# homeboard6.net
KiCad netlist of a schematic drawn in EAGLE
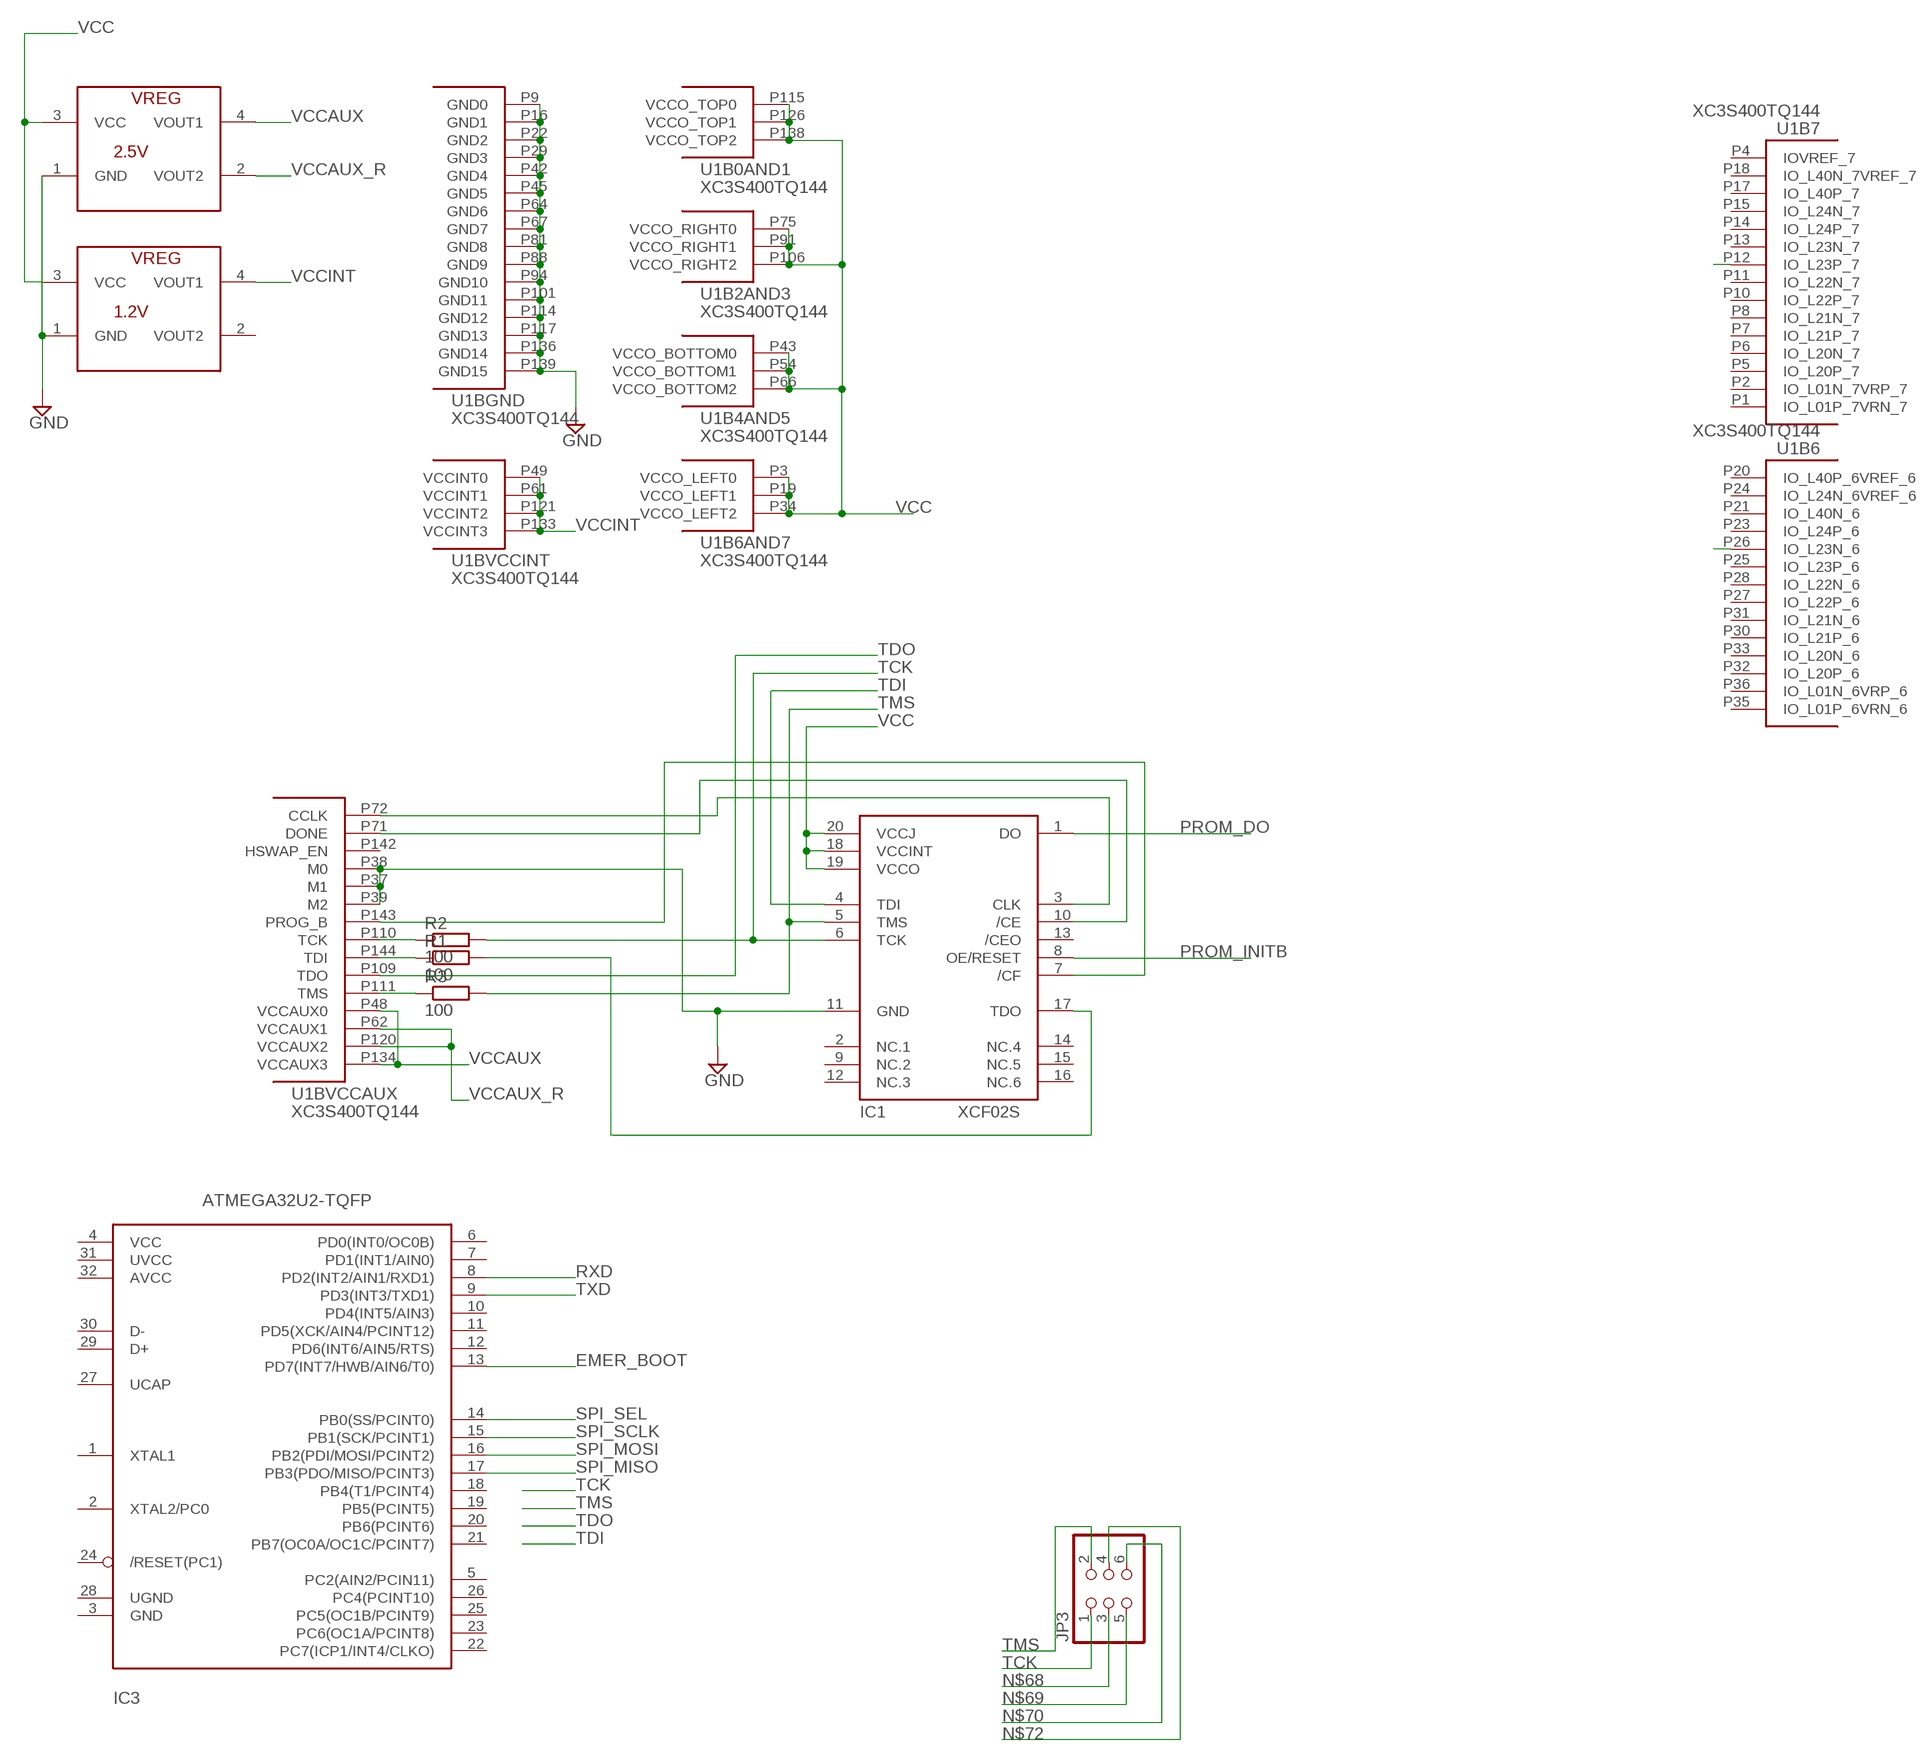
[diagram p0: schematic, sheet 1, part 1 of 3]
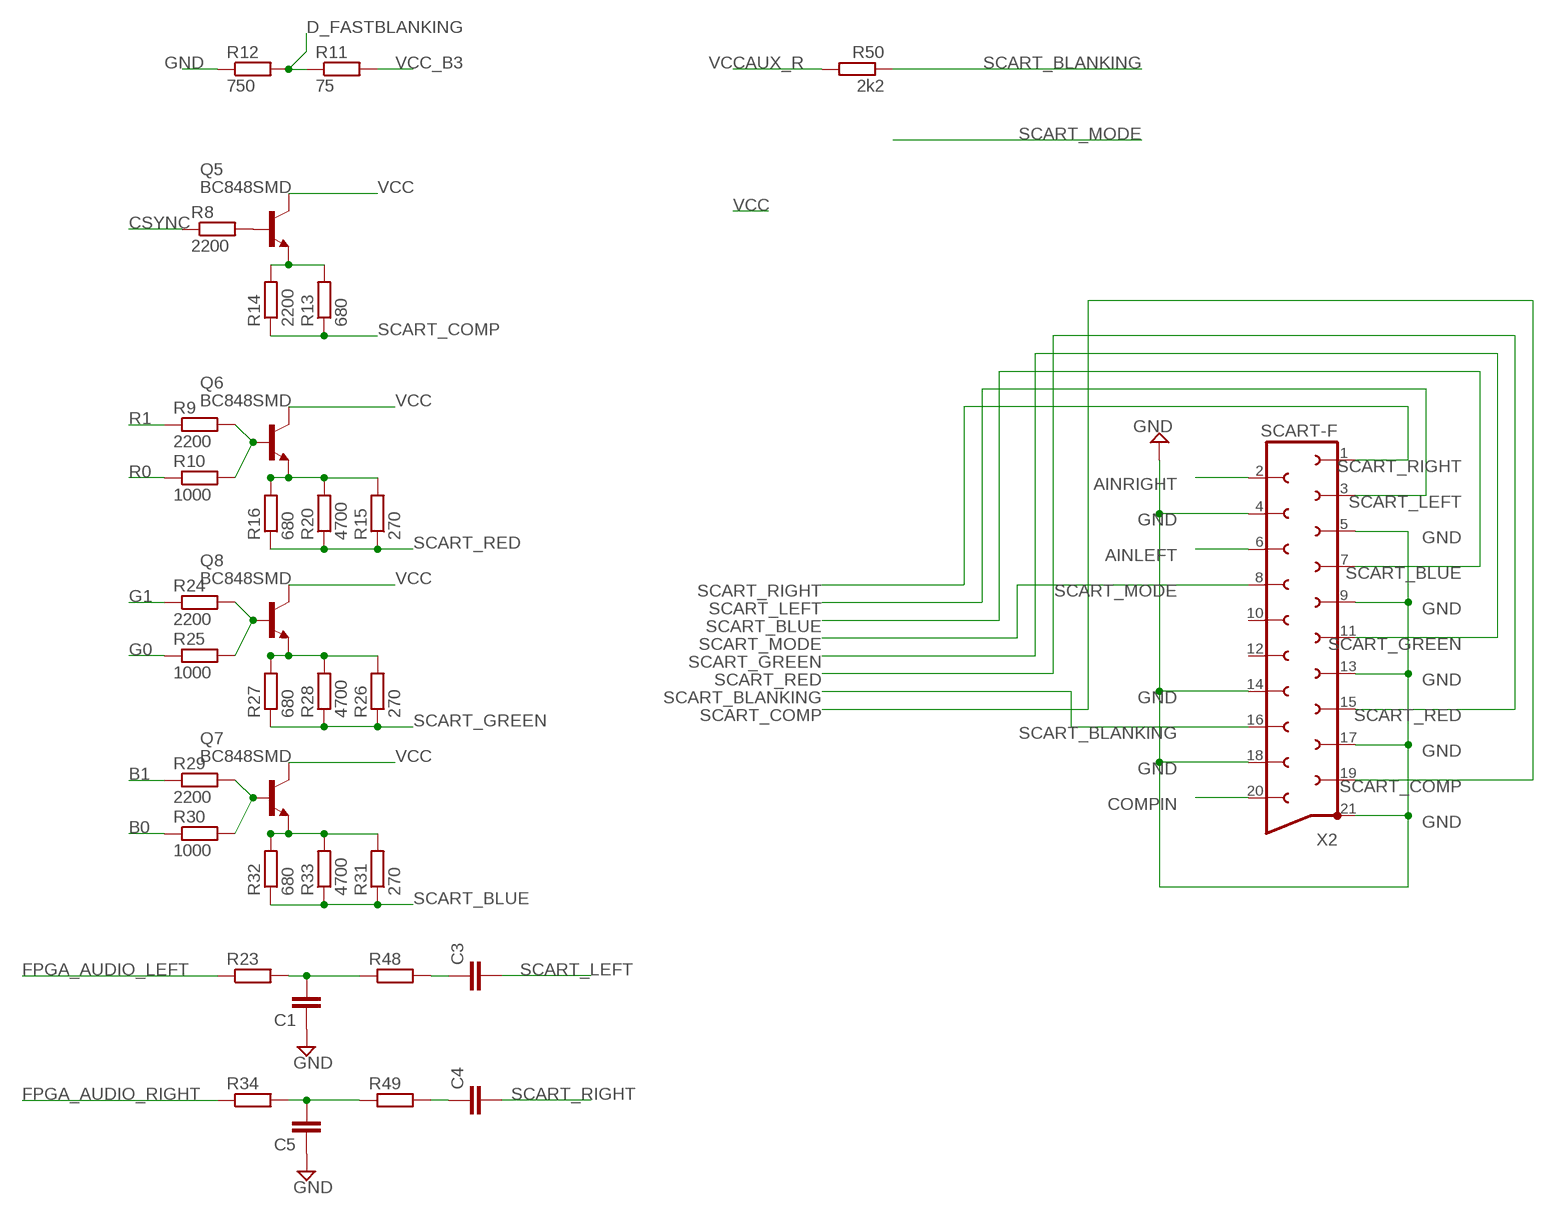
[diagram p1: schematic, sheet 1, part 2 of 3]
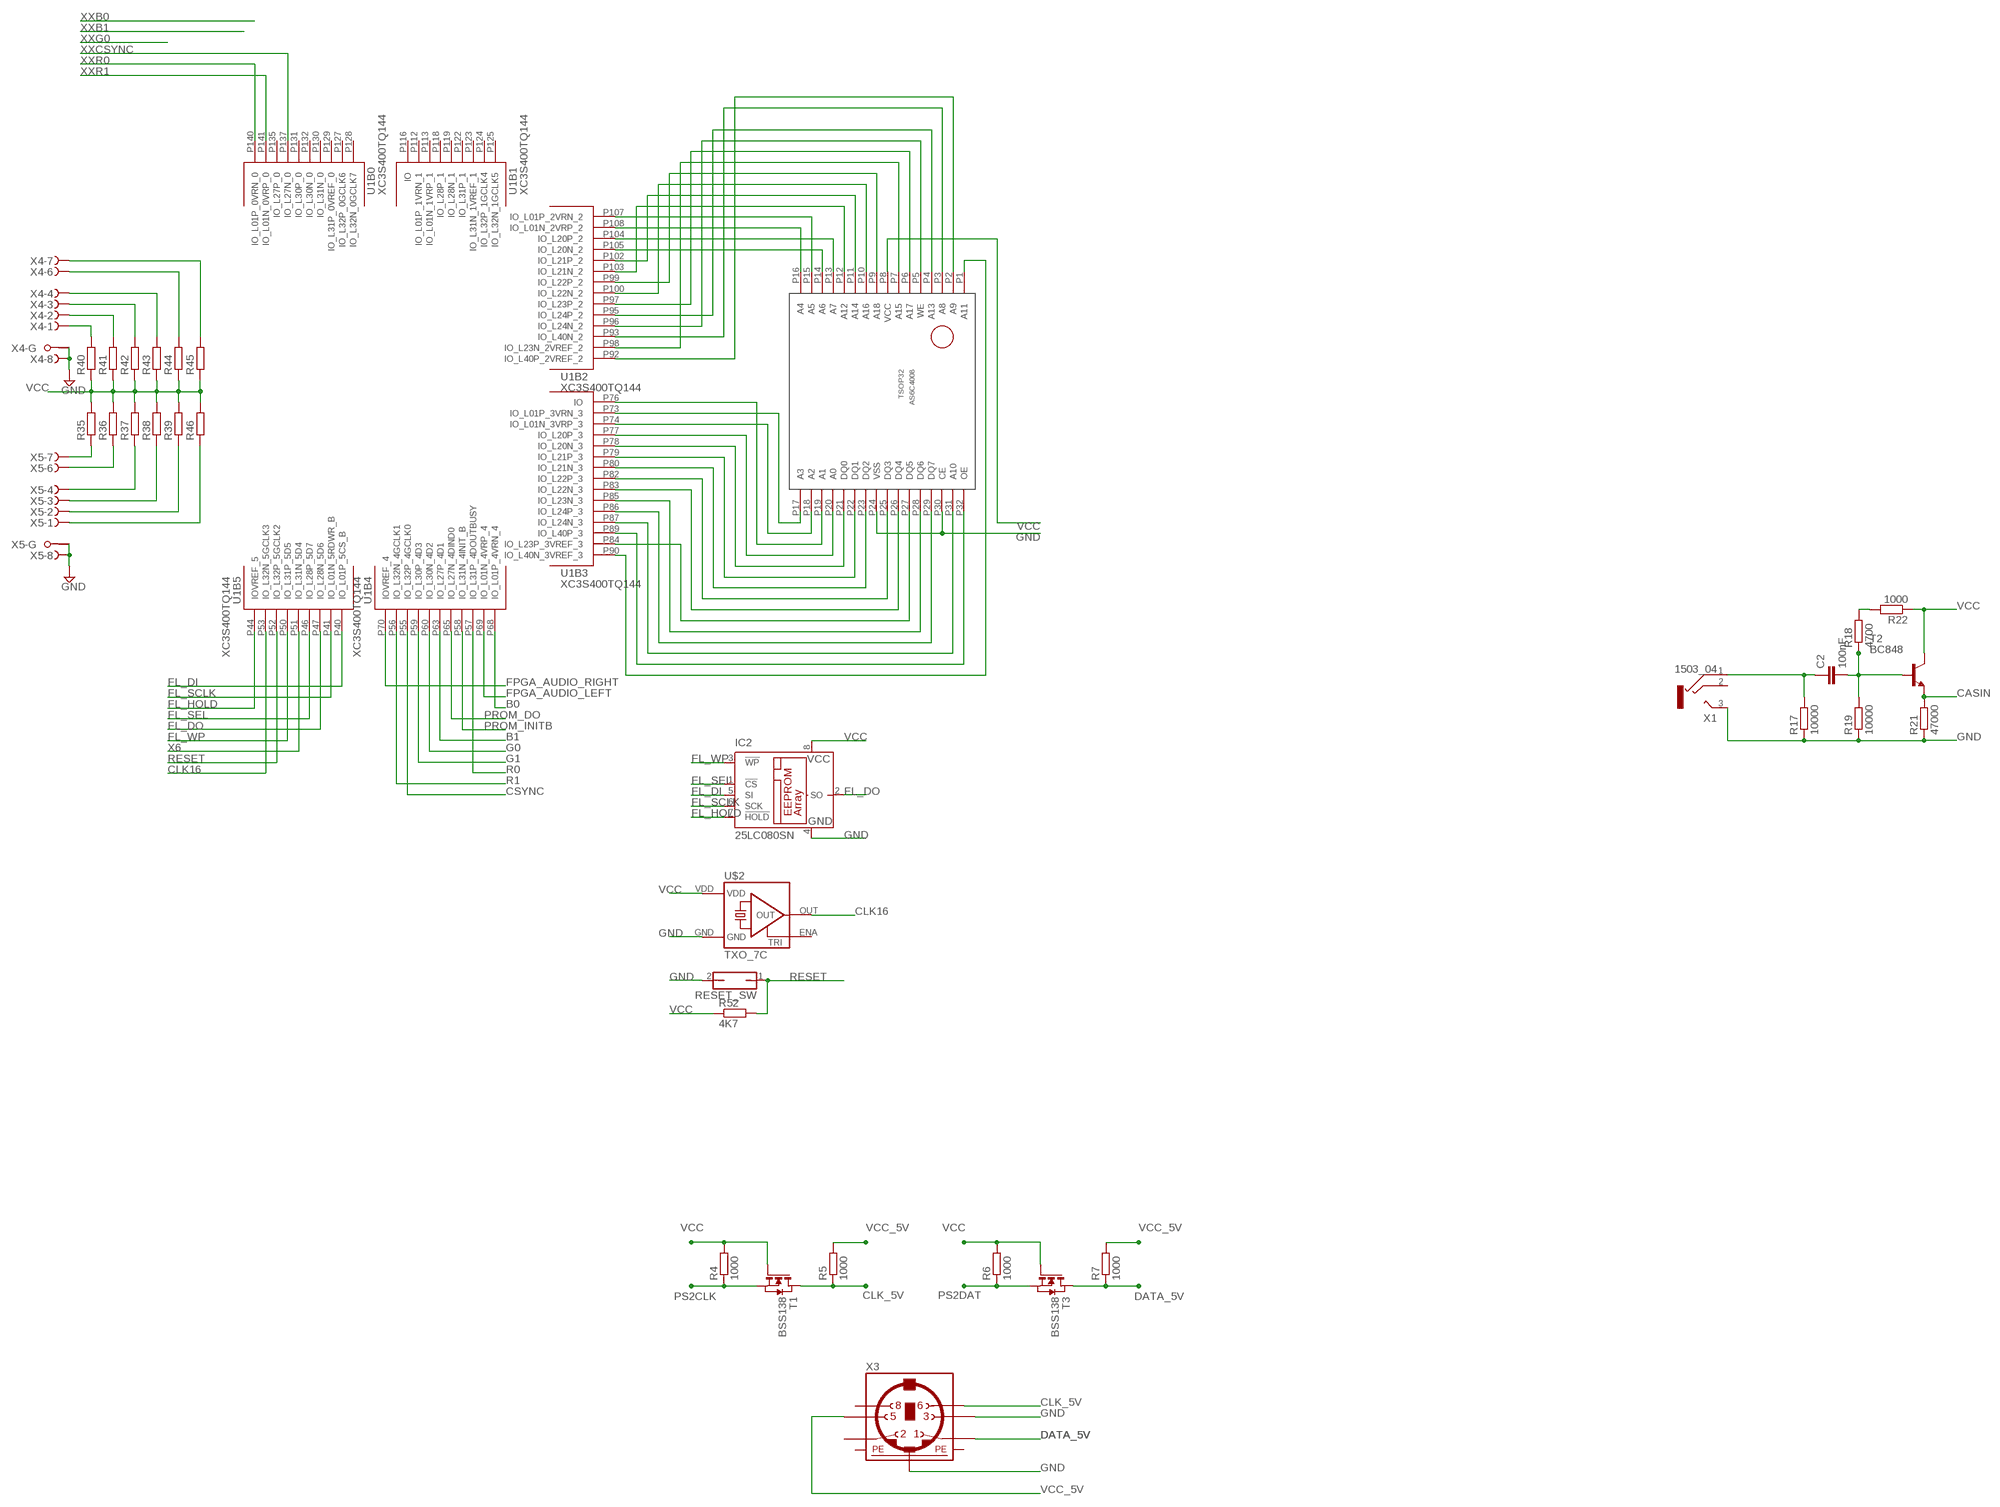
[diagram p2: schematic, sheet 1, part 3 of 3]

(export (version "E")
  (design (tool "Eeschema 10.0.6"))
  (components
    (comp (ref "C1")
      (value "C-EUC0603")
      (footprint "eagle-import:C0603")
      (libsource (lib "eagle-import") (part "C-EUC0603"))
    )
    (comp (ref "C2")
      (value "100nF")
      (footprint "eagle-import:C0603")
      (libsource (lib "eagle-import") (part "C-EUC0603"))
    )
    (comp (ref "C3")
      (value "C-EUC0603")
      (footprint "eagle-import:C0603")
      (libsource (lib "eagle-import") (part "C-EUC0603"))
    )
    (comp (ref "C4")
      (value "C-EUC0603")
      (footprint "eagle-import:C0603")
      (libsource (lib "eagle-import") (part "C-EUC0603"))
    )
    (comp (ref "C5")
      (value "C-EUC0603")
      (footprint "eagle-import:C0603")
      (libsource (lib "eagle-import") (part "C-EUC0603"))
    )
    (comp (ref "IC1")
      (value "XCF02S")
      (footprint "eagle-import:VO20")
      (libsource (lib "eagle-import") (part "XCF02S"))
    )
    (comp (ref "IC2")
      (value "25LC080SN")
      (footprint "eagle-import:SO-08")
      (fields (field (name "MF") "MICROCHIP") (field (name "MPN") "25LC080/SN"))
      (libsource (lib "eagle-import") (part "25SNLC080"))
    )
    (comp (ref "IC3")
      (value "ATMEGA32U2-TQFP")
      (footprint "eagle-import:TQFP32-08")
      (libsource (lib "eagle-import") (part "ATMEGA32U2-TQFP"))
    )
    (comp (ref "JP3")
      (value "PINHD-2X3")
      (footprint "eagle-import:2X03")
      (libsource (lib "eagle-import") (part "PINHD-2X3"))
    )
    (comp (ref "Q5")
      (value "BC848SMD")
      (footprint "eagle-import:SOT23")
      (libsource (lib "eagle-import") (part "BC848SMD"))
    )
    (comp (ref "Q6")
      (value "BC848SMD")
      (footprint "eagle-import:SOT23")
      (libsource (lib "eagle-import") (part "BC848SMD"))
    )
    (comp (ref "Q7")
      (value "BC848SMD")
      (footprint "eagle-import:SOT23")
      (libsource (lib "eagle-import") (part "BC848SMD"))
    )
    (comp (ref "Q8")
      (value "BC848SMD")
      (footprint "eagle-import:SOT23")
      (libsource (lib "eagle-import") (part "BC848SMD"))
    )
    (comp (ref "R1")
      (value "100")
      (footprint "eagle-import:R0805")
      (libsource (lib "eagle-import") (part "R-EU_R0805"))
    )
    (comp (ref "R2")
      (value "100")
      (footprint "eagle-import:R0805")
      (libsource (lib "eagle-import") (part "R-EU_R0805"))
    )
    (comp (ref "R3")
      (value "100")
      (footprint "eagle-import:R0805")
      (libsource (lib "eagle-import") (part "R-EU_R0805"))
    )
    (comp (ref "R4")
      (value "1000")
      (footprint "eagle-import:R0805")
      (libsource (lib "eagle-import") (part "R-EU_R0805"))
    )
    (comp (ref "R5")
      (value "1000")
      (footprint "eagle-import:R0805")
      (libsource (lib "eagle-import") (part "R-EU_R0805"))
    )
    (comp (ref "R6")
      (value "1000")
      (footprint "eagle-import:R0805")
      (libsource (lib "eagle-import") (part "R-EU_R0805"))
    )
    (comp (ref "R7")
      (value "1000")
      (footprint "eagle-import:R0805")
      (libsource (lib "eagle-import") (part "R-EU_R0805"))
    )
    (comp (ref "R8")
      (value "2200")
      (footprint "eagle-import:R0805")
      (libsource (lib "eagle-import") (part "R-EU_R0805"))
    )
    (comp (ref "R9")
      (value "2200")
      (footprint "eagle-import:R0805")
      (libsource (lib "eagle-import") (part "R-EU_R0805"))
    )
    (comp (ref "R10")
      (value "1000")
      (footprint "eagle-import:R0805")
      (libsource (lib "eagle-import") (part "R-EU_R0805"))
    )
    (comp (ref "R11")
      (value "75")
      (footprint "eagle-import:R0805")
      (libsource (lib "eagle-import") (part "R-EU_R0805"))
    )
    (comp (ref "R12")
      (value "750")
      (footprint "eagle-import:R0805")
      (libsource (lib "eagle-import") (part "R-EU_R0805"))
    )
    (comp (ref "R13")
      (value "680")
      (footprint "eagle-import:R0805")
      (libsource (lib "eagle-import") (part "R-EU_R0805"))
    )
    (comp (ref "R14")
      (value "2200")
      (footprint "eagle-import:R0805")
      (libsource (lib "eagle-import") (part "R-EU_R0805"))
    )
    (comp (ref "R15")
      (value "270")
      (footprint "eagle-import:R0805")
      (libsource (lib "eagle-import") (part "R-EU_R0805"))
    )
    (comp (ref "R16")
      (value "680")
      (footprint "eagle-import:R0805")
      (libsource (lib "eagle-import") (part "R-EU_R0805"))
    )
    (comp (ref "R17")
      (value "10000")
      (footprint "eagle-import:R0805")
      (libsource (lib "eagle-import") (part "R-EU_R0805"))
    )
    (comp (ref "R18")
      (value "4700")
      (footprint "eagle-import:R0805")
      (libsource (lib "eagle-import") (part "R-EU_R0805"))
    )
    (comp (ref "R19")
      (value "10000")
      (footprint "eagle-import:R0805")
      (libsource (lib "eagle-import") (part "R-EU_R0805"))
    )
    (comp (ref "R20")
      (value "4700")
      (footprint "eagle-import:R0805")
      (libsource (lib "eagle-import") (part "R-EU_R0805"))
    )
    (comp (ref "R21")
      (value "47000")
      (footprint "eagle-import:R0805")
      (libsource (lib "eagle-import") (part "R-EU_R0805"))
    )
    (comp (ref "R22")
      (value "1000")
      (footprint "eagle-import:R0805")
      (libsource (lib "eagle-import") (part "R-EU_R0805"))
    )
    (comp (ref "R23")
      (value "R-EU_M0805")
      (footprint "eagle-import:M0805")
      (libsource (lib "eagle-import") (part "resistor_R-EU_M0805"))
    )
    (comp (ref "R24")
      (value "2200")
      (footprint "eagle-import:R0805")
      (libsource (lib "eagle-import") (part "R-EU_R0805"))
    )
    (comp (ref "R25")
      (value "1000")
      (footprint "eagle-import:R0805")
      (libsource (lib "eagle-import") (part "R-EU_R0805"))
    )
    (comp (ref "R26")
      (value "270")
      (footprint "eagle-import:R0805")
      (libsource (lib "eagle-import") (part "R-EU_R0805"))
    )
    (comp (ref "R27")
      (value "680")
      (footprint "eagle-import:R0805")
      (libsource (lib "eagle-import") (part "R-EU_R0805"))
    )
    (comp (ref "R28")
      (value "4700")
      (footprint "eagle-import:R0805")
      (libsource (lib "eagle-import") (part "R-EU_R0805"))
    )
    (comp (ref "R29")
      (value "2200")
      (footprint "eagle-import:R0805")
      (libsource (lib "eagle-import") (part "R-EU_R0805"))
    )
    (comp (ref "R30")
      (value "1000")
      (footprint "eagle-import:R0805")
      (libsource (lib "eagle-import") (part "R-EU_R0805"))
    )
    (comp (ref "R31")
      (value "270")
      (footprint "eagle-import:R0805")
      (libsource (lib "eagle-import") (part "R-EU_R0805"))
    )
    (comp (ref "R32")
      (value "680")
      (footprint "eagle-import:R0805")
      (libsource (lib "eagle-import") (part "R-EU_R0805"))
    )
    (comp (ref "R33")
      (value "4700")
      (footprint "eagle-import:R0805")
      (libsource (lib "eagle-import") (part "R-EU_R0805"))
    )
    (comp (ref "R34")
      (value "R-EU_M0805")
      (footprint "eagle-import:M0805")
      (libsource (lib "eagle-import") (part "resistor_R-EU_M0805"))
    )
    (comp (ref "R35")
      (value "R-EU_M0805")
      (footprint "eagle-import:M0805")
      (libsource (lib "eagle-import") (part "resistor_R-EU_M0805"))
    )
    (comp (ref "R36")
      (value "R-EU_M0805")
      (footprint "eagle-import:M0805")
      (libsource (lib "eagle-import") (part "resistor_R-EU_M0805"))
    )
    (comp (ref "R37")
      (value "R-EU_M0805")
      (footprint "eagle-import:M0805")
      (libsource (lib "eagle-import") (part "resistor_R-EU_M0805"))
    )
    (comp (ref "R38")
      (value "R-EU_M0805")
      (footprint "eagle-import:M0805")
      (libsource (lib "eagle-import") (part "resistor_R-EU_M0805"))
    )
    (comp (ref "R39")
      (value "R-EU_M0805")
      (footprint "eagle-import:M0805")
      (libsource (lib "eagle-import") (part "resistor_R-EU_M0805"))
    )
    (comp (ref "R40")
      (value "R-EU_M0805")
      (footprint "eagle-import:M0805")
      (libsource (lib "eagle-import") (part "resistor_R-EU_M0805"))
    )
    (comp (ref "R41")
      (value "R-EU_M0805")
      (footprint "eagle-import:M0805")
      (libsource (lib "eagle-import") (part "resistor_R-EU_M0805"))
    )
    (comp (ref "R42")
      (value "R-EU_M0805")
      (footprint "eagle-import:M0805")
      (libsource (lib "eagle-import") (part "resistor_R-EU_M0805"))
    )
    (comp (ref "R43")
      (value "R-EU_M0805")
      (footprint "eagle-import:M0805")
      (libsource (lib "eagle-import") (part "resistor_R-EU_M0805"))
    )
    (comp (ref "R44")
      (value "R-EU_M0805")
      (footprint "eagle-import:M0805")
      (libsource (lib "eagle-import") (part "resistor_R-EU_M0805"))
    )
    (comp (ref "R45")
      (value "R-EU_M0805")
      (footprint "eagle-import:M0805")
      (libsource (lib "eagle-import") (part "resistor_R-EU_M0805"))
    )
    (comp (ref "R46")
      (value "R-EU_M0805")
      (footprint "eagle-import:M0805")
      (libsource (lib "eagle-import") (part "resistor_R-EU_M0805"))
    )
    (comp (ref "R48")
      (value "R-EU_M0805")
      (footprint "eagle-import:M0805")
      (libsource (lib "eagle-import") (part "resistor_R-EU_M0805"))
    )
    (comp (ref "R49")
      (value "R-EU_M0805")
      (footprint "eagle-import:M0805")
      (libsource (lib "eagle-import") (part "resistor_R-EU_M0805"))
    )
    (comp (ref "R50")
      (value "2k2")
      (footprint "eagle-import:M0805")
      (libsource (lib "eagle-import") (part "resistor_R-EU_M0805"))
    )
    (comp (ref "R52")
      (value "4K7")
      (footprint "eagle-import:M0805")
      (libsource (lib "eagle-import") (part "resistor_R-EU_M0805"))
    )
    (comp (ref "REG1.2")
      (value "1.2V")
      (footprint "eagle-import:SOT223")
      (libsource (lib "eagle-import") (part "NX1117"))
    )
    (comp (ref "REG2.5")
      (value "2.5V")
      (footprint "eagle-import:SOT223")
      (libsource (lib "eagle-import") (part "NX1117"))
    )
    (comp (ref "RESET_SW")
      (value "JP1Q")
      (footprint "eagle-import:JP1")
      (libsource (lib "eagle-import") (part "JP1Q"))
    )
    (comp (ref "T1")
      (value "BSS138")
      (footprint "eagle-import:SOT-23")
      (libsource (lib "eagle-import") (part "NMOSSOT23"))
    )
    (comp (ref "T2")
      (value "BC848")
      (footprint "eagle-import:SOT23")
      (libsource (lib "eagle-import") (part "BC848"))
    )
    (comp (ref "T3")
      (value "BSS138")
      (footprint "eagle-import:SOT-23")
      (libsource (lib "eagle-import") (part "NMOSSOT23"))
    )
    (comp (ref "U$1")
      (value "AS6C4008")
      (footprint "eagle-import:TSOP32")
      (libsource (lib "eagle-import") (part "AS6C4008"))
    )
    (comp (ref "U$2")
      (value "TXO_7C")
      (footprint "eagle-import:OSC_7C")
      (libsource (lib "eagle-import") (part "TXO_7C"))
    )
    (comp (ref "U1")
      (value "XC3S400TQ144")
      (footprint "eagle-import:TQ144")
      (libsource (lib "eagle-import") (part "XC3S400TQ144"))
    )
    (comp (ref "X1")
      (value "1503_04")
      (footprint "eagle-import:1503_04")
      (libsource (lib "eagle-import") (part "1503_04"))
    )
    (comp (ref "X2")
      (value "SCART-F")
      (footprint "eagle-import:SCART-F")
      (libsource (lib "eagle-import") (part "SCART-F"))
    )
    (comp (ref "X3")
      (value "MINI_DIN_6")
      (footprint "eagle-import:M_DIN6")
      (libsource (lib "eagle-import") (part "MINI_DIN_6"))
    )
    (comp (ref "X4")
      (value "F09HPS")
      (footprint "eagle-import:F09HP")
      (libsource (lib "eagle-import") (part "F09HPS"))
    )
    (comp (ref "X5")
      (value "F09HPS")
      (footprint "eagle-import:F09HP")
      (libsource (lib "eagle-import") (part "F09HPS"))
    )
  )
  (nets
    (net (code "1") (name "/AINLEFT") (class "Default")
      (node (ref "X2") (pin "6") (pinfunction "6_6") (pintype "passive"))
    )
    (net (code "2") (name "/AINRIGHT") (class "Default")
      (node (ref "X2") (pin "2") (pinfunction "2_2") (pintype "passive"))
    )
    (net (code "3") (name "/B0") (class "Default")
      (node (ref "R30") (pin "1") (pinfunction "1_1") (pintype "passive"))
      (node (ref "U1") (pin "P68") (pinfunction "IO_L01P_4VRN_4_P68") (pintype "bidirectional"))
    )
    (net (code "4") (name "/B1") (class "Default")
      (node (ref "R29") (pin "1") (pinfunction "1_1") (pintype "passive"))
      (node (ref "U1") (pin "P63") (pinfunction "IO_L27P_4D1_P63") (pintype "bidirectional"))
    )
    (net (code "5") (name "/CASIN") (class "Default")
      (node (ref "R21") (pin "2") (pinfunction "2_2") (pintype "passive"))
      (node (ref "T2") (pin "2") (pinfunction "E_2") (pintype "passive"))
    )
    (net (code "6") (name "/CLK16") (class "Default")
      (node (ref "U$2") (pin "OUT") (pinfunction "OUT_OUT") (pintype "output"))
      (node (ref "U1") (pin "P53") (pinfunction "IO_L32N_5GCLK3_P53") (pintype "bidirectional"))
    )
    (net (code "7") (name "/CLK_5V") (class "Default")
      (node (ref "R5") (pin "1") (pinfunction "1_1") (pintype "passive"))
      (node (ref "T1") (pin "1") (pinfunction "D_1") (pintype "passive"))
      (node (ref "X3") (pin "6") (pinfunction "6_6") (pintype "passive"))
    )
    (net (code "8") (name "/COMPIN") (class "Default")
      (node (ref "X2") (pin "20") (pinfunction "20_20") (pintype "passive"))
    )
    (net (code "9") (name "/CSYNC") (class "Default")
      (node (ref "R8") (pin "1") (pinfunction "1_1") (pintype "passive"))
      (node (ref "U1") (pin "P55") (pinfunction "IO_L32P_4GCLK0_P55") (pintype "bidirectional"))
    )
    (net (code "10") (name "/DATA_5V") (class "Default")
      (node (ref "R7") (pin "1") (pinfunction "1_1") (pintype "passive"))
      (node (ref "T3") (pin "1") (pinfunction "D_1") (pintype "passive"))
      (node (ref "X3") (pin "1") (pinfunction "1_1") (pintype "passive"))
    )
    (net (code "11") (name "/D_FASTBLANKING") (class "Default")
      (node (ref "R11") (pin "1") (pinfunction "1_1") (pintype "passive"))
      (node (ref "R12") (pin "2") (pinfunction "2_2") (pintype "passive"))
    )
    (net (code "12") (name "/EMER_BOOT") (class "Default")
      (node (ref "IC3") (pin "13") (pinfunction "PD7(INT7/HWB/AIN6/T0)_13") (pintype "bidirectional"))
    )
    (net (code "13") (name "/FL_DI") (class "Default")
      (node (ref "IC2") (pin "5") (pinfunction "SI_5") (pintype "input"))
      (node (ref "U1") (pin "P40") (pinfunction "IO_L01P_5CS_B_P40") (pintype "bidirectional"))
    )
    (net (code "14") (name "/FL_DO") (class "Default")
      (node (ref "IC2") (pin "2") (pinfunction "SO_2") (pintype "bidirectional"))
      (node (ref "U1") (pin "P47") (pinfunction "IO_L28N_5D6_P47") (pintype "bidirectional"))
    )
    (net (code "15") (name "/FL_HOLD") (class "Default")
      (node (ref "IC2") (pin "7") (pinfunction "~{HOLD}_7") (pintype "input"))
      (node (ref "U1") (pin "P44") (pinfunction "IOVREF_5_P44") (pintype "bidirectional"))
    )
    (net (code "16") (name "/FL_SCLK") (class "Default")
      (node (ref "IC2") (pin "6") (pinfunction "SCK_6") (pintype "input"))
      (node (ref "U1") (pin "P41") (pinfunction "IO_L01N_5RDWR_B_P41") (pintype "bidirectional"))
    )
    (net (code "17") (name "/FL_SEL") (class "Default")
      (node (ref "IC2") (pin "1") (pinfunction "~{CS}_1") (pintype "input"))
      (node (ref "U1") (pin "P46") (pinfunction "IO_L28P_5D7_P46") (pintype "bidirectional"))
    )
    (net (code "18") (name "/FL_WP") (class "Default")
      (node (ref "IC2") (pin "3") (pinfunction "~{WP}_3") (pintype "input"))
      (node (ref "U1") (pin "P50") (pinfunction "IO_L31P_5D5_P50") (pintype "bidirectional"))
    )
    (net (code "19") (name "/FPGA_AUDIO_LEFT") (class "Default")
      (node (ref "R23") (pin "1") (pinfunction "1_1") (pintype "passive"))
      (node (ref "U1") (pin "P69") (pinfunction "IO_L01N_4VRP_4_P69") (pintype "bidirectional"))
    )
    (net (code "20") (name "/FPGA_AUDIO_RIGHT") (class "Default")
      (node (ref "R34") (pin "1") (pinfunction "1_1") (pintype "passive"))
      (node (ref "U1") (pin "P70") (pinfunction "IOVREF_4_P70") (pintype "bidirectional"))
    )
    (net (code "21") (name "/G0") (class "Default")
      (node (ref "R25") (pin "1") (pinfunction "1_1") (pintype "passive"))
      (node (ref "U1") (pin "P60") (pinfunction "IO_L30N_4D2_P60") (pintype "bidirectional"))
    )
    (net (code "22") (name "/G1") (class "Default")
      (node (ref "R24") (pin "1") (pinfunction "1_1") (pintype "passive"))
      (node (ref "U1") (pin "P59") (pinfunction "IO_L30P_4D3_P59") (pintype "bidirectional"))
    )
    (net (code "23") (name "/N$68") (class "Default")
      (node (ref "JP3") (pin "3") (pinfunction "3_3") (pintype "passive"))
    )
    (net (code "24") (name "/N$69") (class "Default")
      (node (ref "JP3") (pin "5") (pinfunction "5_5") (pintype "passive"))
    )
    (net (code "25") (name "/N$70") (class "Default")
      (node (ref "JP3") (pin "6") (pinfunction "6_6") (pintype "passive"))
    )
    (net (code "26") (name "/N$72") (class "Default")
      (node (ref "JP3") (pin "4") (pinfunction "4_4") (pintype "passive"))
    )
    (net (code "27") (name "/PE1") (class "Default")
      (node (ref "X3") (pin "SH1") (pinfunction "PE1_SH1") (pintype "power_in"))
    )
    (net (code "28") (name "/PE3") (class "Default")
      (node (ref "X3") (pin "SH3") (pinfunction "PE3_SH3") (pintype "power_in"))
    )
    (net (code "29") (name "/PROM_DO") (class "Default")
      (node (ref "IC1") (pin "1") (pinfunction "DO_1") (pintype "bidirectional"))
      (node (ref "U1") (pin "P65") (pinfunction "IO_L27N_4DIND0_P65") (pintype "bidirectional"))
    )
    (net (code "30") (name "/PROM_INITB") (class "Default")
      (node (ref "IC1") (pin "8") (pinfunction "OE/RESET_8") (pintype "bidirectional"))
      (node (ref "U1") (pin "P58") (pinfunction "IO_L31N_4INIT_B_P58") (pintype "bidirectional"))
    )
    (net (code "31") (name "/PS2CLK") (class "Default")
      (node (ref "R4") (pin "1") (pinfunction "1_1") (pintype "passive"))
      (node (ref "T1") (pin "2") (pinfunction "S_2") (pintype "passive"))
    )
    (net (code "32") (name "/PS2DAT") (class "Default")
      (node (ref "R6") (pin "1") (pinfunction "1_1") (pintype "passive"))
      (node (ref "T3") (pin "2") (pinfunction "S_2") (pintype "passive"))
    )
    (net (code "33") (name "/R0") (class "Default")
      (node (ref "R10") (pin "1") (pinfunction "1_1") (pintype "passive"))
      (node (ref "U1") (pin "P57") (pinfunction "IO_L31P_4DOUTBUSY_P57") (pintype "bidirectional"))
    )
    (net (code "34") (name "/R1") (class "Default")
      (node (ref "R9") (pin "1") (pinfunction "1_1") (pintype "passive"))
      (node (ref "U1") (pin "P56") (pinfunction "IO_L32N_4GCLK1_P56") (pintype "bidirectional"))
    )
    (net (code "35") (name "/RESET") (class "Default")
      (node (ref "R52") (pin "2") (pinfunction "2_2") (pintype "passive"))
      (node (ref "RESET_SW") (pin "1") (pinfunction "1_1") (pintype "passive"))
      (node (ref "U1") (pin "P52") (pinfunction "IO_L32P_5GCLK2_P52") (pintype "bidirectional"))
    )
    (net (code "36") (name "/RXD") (class "Default")
      (node (ref "IC3") (pin "8") (pinfunction "PD2(INT2/AIN1/RXD1)_8") (pintype "bidirectional"))
    )
    (net (code "37") (name "/SCART_BLANKING") (class "Default")
      (node (ref "R50") (pin "1") (pinfunction "1_1") (pintype "passive"))
      (node (ref "X2") (pin "16") (pinfunction "16_16") (pintype "passive"))
    )
    (net (code "38") (name "/SCART_BLUE") (class "Default")
      (node (ref "R31") (pin "1") (pinfunction "1_1") (pintype "passive"))
      (node (ref "R32") (pin "1") (pinfunction "1_1") (pintype "passive"))
      (node (ref "R33") (pin "1") (pinfunction "1_1") (pintype "passive"))
      (node (ref "X2") (pin "7") (pinfunction "7_7") (pintype "passive"))
    )
    (net (code "39") (name "/SCART_COMP") (class "Default")
      (node (ref "R13") (pin "1") (pinfunction "1_1") (pintype "passive"))
      (node (ref "R14") (pin "1") (pinfunction "1_1") (pintype "passive"))
      (node (ref "X2") (pin "19") (pinfunction "19_19") (pintype "passive"))
    )
    (net (code "40") (name "/SCART_GREEN") (class "Default")
      (node (ref "R26") (pin "1") (pinfunction "1_1") (pintype "passive"))
      (node (ref "R27") (pin "1") (pinfunction "1_1") (pintype "passive"))
      (node (ref "R28") (pin "1") (pinfunction "1_1") (pintype "passive"))
      (node (ref "X2") (pin "11") (pinfunction "11_11") (pintype "passive"))
    )
    (net (code "41") (name "/SCART_LEFT") (class "Default")
      (node (ref "C3") (pin "2") (pinfunction "2_2") (pintype "passive"))
      (node (ref "X2") (pin "3") (pinfunction "3_3") (pintype "passive"))
    )
    (net (code "42") (name "/SCART_MODE") (class "Default")
      (node (ref "X2") (pin "8") (pinfunction "8_8") (pintype "passive"))
    )
    (net (code "43") (name "/SCART_RED") (class "Default")
      (node (ref "R15") (pin "1") (pinfunction "1_1") (pintype "passive"))
      (node (ref "R16") (pin "1") (pinfunction "1_1") (pintype "passive"))
      (node (ref "R20") (pin "1") (pinfunction "1_1") (pintype "passive"))
      (node (ref "X2") (pin "15") (pinfunction "15_15") (pintype "passive"))
    )
    (net (code "44") (name "/SCART_RIGHT") (class "Default")
      (node (ref "C4") (pin "2") (pinfunction "2_2") (pintype "passive"))
      (node (ref "X2") (pin "1") (pinfunction "1_1") (pintype "passive"))
    )
    (net (code "45") (name "/SPI_MISO") (class "Default")
      (node (ref "IC3") (pin "17") (pinfunction "PB3(PDO/MISO/PCINT3)_17") (pintype "bidirectional"))
    )
    (net (code "46") (name "/SPI_MOSI") (class "Default")
      (node (ref "IC3") (pin "16") (pinfunction "PB2(PDI/MOSI/PCINT2)_16") (pintype "bidirectional"))
    )
    (net (code "47") (name "/SPI_SCLK") (class "Default")
      (node (ref "IC3") (pin "15") (pinfunction "PB1(SCK/PCINT1)_15") (pintype "bidirectional"))
    )
    (net (code "48") (name "/SPI_SEL") (class "Default")
      (node (ref "IC3") (pin "14") (pinfunction "PB0(SS/PCINT0)_14") (pintype "bidirectional"))
    )
    (net (code "49") (name "/TCK") (class "Default")
      (node (ref "IC1") (pin "6") (pinfunction "TCK_6") (pintype "bidirectional"))
      (node (ref "JP3") (pin "1") (pinfunction "1_1") (pintype "passive"))
      (node (ref "R2") (pin "2") (pinfunction "2_2") (pintype "passive"))
    )
    (net (code "50") (name "/TDI") (class "Default")
      (node (ref "IC1") (pin "4") (pinfunction "TDI_4") (pintype "bidirectional"))
    )
    (net (code "51") (name "/TDO") (class "Default")
      (node (ref "U1") (pin "P109") (pinfunction "TDO_P109") (pintype "bidirectional"))
    )
    (net (code "52") (name "/TMS") (class "Default")
      (node (ref "IC1") (pin "5") (pinfunction "TMS_5") (pintype "bidirectional"))
      (node (ref "JP3") (pin "2") (pinfunction "2_2") (pintype "passive"))
      (node (ref "R3") (pin "2") (pinfunction "2_2") (pintype "passive"))
    )
    (net (code "53") (name "/TXD") (class "Default")
      (node (ref "IC3") (pin "9") (pinfunction "PD3(INT3/TXD1)_9") (pintype "bidirectional"))
    )
    (net (code "54") (name "/VCC") (class "Default")
      (node (ref "IC1") (pin "18") (pinfunction "VCCINT_18") (pintype "bidirectional"))
      (node (ref "IC1") (pin "19") (pinfunction "VCCO_19") (pintype "bidirectional"))
      (node (ref "IC1") (pin "20") (pinfunction "VCCJ_20") (pintype "bidirectional"))
      (node (ref "IC2") (pin "8") (pinfunction "VCC_8") (pintype "power_in"))
      (node (ref "Q5") (pin "3") (pinfunction "C_3") (pintype "passive"))
      (node (ref "Q6") (pin "3") (pinfunction "C_3") (pintype "passive"))
      (node (ref "Q7") (pin "3") (pinfunction "C_3") (pintype "passive"))
      (node (ref "Q8") (pin "3") (pinfunction "C_3") (pintype "passive"))
      (node (ref "R22") (pin "1") (pinfunction "1_1") (pintype "passive"))
      (node (ref "R35") (pin "2") (pinfunction "2_2") (pintype "passive"))
      (node (ref "R36") (pin "2") (pinfunction "2_2") (pintype "passive"))
      (node (ref "R37") (pin "2") (pinfunction "2_2") (pintype "passive"))
      (node (ref "R38") (pin "2") (pinfunction "2_2") (pintype "passive"))
      (node (ref "R39") (pin "2") (pinfunction "2_2") (pintype "passive"))
      (node (ref "R4") (pin "2") (pinfunction "2_2") (pintype "passive"))
      (node (ref "R40") (pin "1") (pinfunction "1_1") (pintype "passive"))
      (node (ref "R41") (pin "1") (pinfunction "1_1") (pintype "passive"))
      (node (ref "R42") (pin "1") (pinfunction "1_1") (pintype "passive"))
      (node (ref "R43") (pin "1") (pinfunction "1_1") (pintype "passive"))
      (node (ref "R44") (pin "1") (pinfunction "1_1") (pintype "passive"))
      (node (ref "R45") (pin "1") (pinfunction "1_1") (pintype "passive"))
      (node (ref "R46") (pin "2") (pinfunction "2_2") (pintype "passive"))
      (node (ref "R52") (pin "1") (pinfunction "1_1") (pintype "passive"))
      (node (ref "R6") (pin "2") (pinfunction "2_2") (pintype "passive"))
      (node (ref "REG1.2") (pin "3") (pinfunction "VCC_3") (pintype "bidirectional"))
      (node (ref "REG2.5") (pin "3") (pinfunction "VCC_3") (pintype "bidirectional"))
      (node (ref "T1") (pin "3") (pinfunction "G_3") (pintype "passive"))
      (node (ref "T2") (pin "3") (pinfunction "C_3") (pintype "passive"))
      (node (ref "T3") (pin "3") (pinfunction "G_3") (pintype "passive"))
      (node (ref "U$1") (pin "P8") (pinfunction "VCC_P8") (pintype "bidirectional"))
      (node (ref "U$2") (pin "VDD") (pinfunction "VDD_VDD") (pintype "power_in"))
      (node (ref "U1") (pin "P106") (pinfunction "VCCO_RIGHT2_P106") (pintype "passive"))
      (node (ref "U1") (pin "P115") (pinfunction "VCCO_TOP0_P115") (pintype "passive"))
      (node (ref "U1") (pin "P126") (pinfunction "VCCO_TOP1_P126") (pintype "passive"))
      (node (ref "U1") (pin "P138") (pinfunction "VCCO_TOP2_P138") (pintype "passive"))
      (node (ref "U1") (pin "P19") (pinfunction "VCCO_LEFT1_P19") (pintype "passive"))
      (node (ref "U1") (pin "P3") (pinfunction "VCCO_LEFT0_P3") (pintype "passive"))
      (node (ref "U1") (pin "P34") (pinfunction "VCCO_LEFT2_P34") (pintype "passive"))
      (node (ref "U1") (pin "P43") (pinfunction "VCCO_BOTTOM0_P43") (pintype "passive"))
      (node (ref "U1") (pin "P54") (pinfunction "VCCO_BOTTOM1_P54") (pintype "passive"))
      (node (ref "U1") (pin "P66") (pinfunction "VCCO_BOTTOM2_P66") (pintype "passive"))
      (node (ref "U1") (pin "P75") (pinfunction "VCCO_RIGHT0_P75") (pintype "passive"))
      (node (ref "U1") (pin "P91") (pinfunction "VCCO_RIGHT1_P91") (pintype "passive"))
    )
    (net (code "55") (name "/VCCAUX") (class "Default")
      (node (ref "REG2.5") (pin "4") (pinfunction "VOUT1_4") (pintype "bidirectional"))
      (node (ref "U1") (pin "P134") (pinfunction "VCCAUX3_P134") (pintype "passive"))
      (node (ref "U1") (pin "P48") (pinfunction "VCCAUX0_P48") (pintype "passive"))
    )
    (net (code "56") (name "/VCCAUX_R") (class "Default")
      (node (ref "R50") (pin "2") (pinfunction "2_2") (pintype "passive"))
      (node (ref "REG2.5") (pin "2") (pinfunction "VOUT2_2") (pintype "bidirectional"))
      (node (ref "U1") (pin "P120") (pinfunction "VCCAUX2_P120") (pintype "passive"))
      (node (ref "U1") (pin "P62") (pinfunction "VCCAUX1_P62") (pintype "passive"))
    )
    (net (code "57") (name "/VCCINT") (class "Default")
      (node (ref "REG1.2") (pin "4") (pinfunction "VOUT1_4") (pintype "bidirectional"))
      (node (ref "U1") (pin "P121") (pinfunction "VCCINT2_P121") (pintype "passive"))
      (node (ref "U1") (pin "P133") (pinfunction "VCCINT3_P133") (pintype "passive"))
      (node (ref "U1") (pin "P49") (pinfunction "VCCINT0_P49") (pintype "passive"))
      (node (ref "U1") (pin "P61") (pinfunction "VCCINT1_P61") (pintype "passive"))
    )
    (net (code "58") (name "/VCC_5V") (class "Default")
      (node (ref "R5") (pin "2") (pinfunction "2_2") (pintype "passive"))
      (node (ref "R7") (pin "2") (pinfunction "2_2") (pintype "passive"))
      (node (ref "X3") (pin "5") (pinfunction "5_5") (pintype "passive"))
    )
    (net (code "59") (name "/VCC_B3") (class "Default")
      (node (ref "R11") (pin "2") (pinfunction "2_2") (pintype "passive"))
    )
    (net (code "60") (name "/X6") (class "Default")
      (node (ref "U1") (pin "P51") (pinfunction "IO_L31N_5D4_P51") (pintype "bidirectional"))
    )
    (net (code "63") (name "/XXCSYNC") (class "Default")
      (node (ref "U1") (pin "P137") (pinfunction "IO_L27N_0_P137") (pintype "bidirectional"))
    )
    (net (code "65") (name "/XXR0") (class "Default")
      (node (ref "U1") (pin "P140") (pinfunction "IO_L01P_0VRN_0_P140") (pintype "bidirectional"))
    )
    (net (code "66") (name "/XXR1") (class "Default")
      (node (ref "U1") (pin "P141") (pinfunction "IO_L01N_0VRP_0_P141") (pintype "bidirectional"))
    )
    (net (code "67") (name "GND") (class "Default")
      (node (ref "C1") (pin "1") (pinfunction "1_1") (pintype "passive"))
      (node (ref "C5") (pin "1") (pinfunction "1_1") (pintype "passive"))
      (node (ref "IC1") (pin "11") (pinfunction "GND_11") (pintype "bidirectional"))
      (node (ref "IC2") (pin "4") (pinfunction "GND_4") (pintype "power_in"))
      (node (ref "R12") (pin "1") (pinfunction "1_1") (pintype "passive"))
      (node (ref "R17") (pin "1") (pinfunction "1_1") (pintype "passive"))
      (node (ref "R19") (pin "1") (pinfunction "1_1") (pintype "passive"))
      (node (ref "R21") (pin "1") (pinfunction "1_1") (pintype "passive"))
      (node (ref "REG1.2") (pin "1") (pinfunction "GND_1") (pintype "bidirectional"))
      (node (ref "REG2.5") (pin "1") (pinfunction "GND_1") (pintype "bidirectional"))
      (node (ref "RESET_SW") (pin "2") (pinfunction "2_2") (pintype "passive"))
      (node (ref "U$1") (pin "P24") (pinfunction "VSS_P24") (pintype "bidirectional"))
      (node (ref "U$1") (pin "P30") (pinfunction "CE_P30") (pintype "bidirectional"))
      (node (ref "U$2") (pin "GND") (pinfunction "GND_GND") (pintype "power_in"))
      (node (ref "U1") (pin "P101") (pinfunction "GND11_P101") (pintype "passive"))
      (node (ref "U1") (pin "P114") (pinfunction "GND12_P114") (pintype "passive"))
      (node (ref "U1") (pin "P117") (pinfunction "GND13_P117") (pintype "passive"))
      (node (ref "U1") (pin "P136") (pinfunction "GND14_P136") (pintype "passive"))
      (node (ref "U1") (pin "P139") (pinfunction "GND15_P139") (pintype "passive"))
      (node (ref "U1") (pin "P16") (pinfunction "GND1_P16") (pintype "passive"))
      (node (ref "U1") (pin "P22") (pinfunction "GND2_P22") (pintype "passive"))
      (node (ref "U1") (pin "P29") (pinfunction "GND3_P29") (pintype "passive"))
      (node (ref "U1") (pin "P37") (pinfunction "M1_P37") (pintype "bidirectional"))
      (node (ref "U1") (pin "P38") (pinfunction "M0_P38") (pintype "bidirectional"))
      (node (ref "U1") (pin "P39") (pinfunction "M2_P39") (pintype "bidirectional"))
      (node (ref "U1") (pin "P42") (pinfunction "GND4_P42") (pintype "passive"))
      (node (ref "U1") (pin "P45") (pinfunction "GND5_P45") (pintype "passive"))
      (node (ref "U1") (pin "P64") (pinfunction "GND6_P64") (pintype "passive"))
      (node (ref "U1") (pin "P67") (pinfunction "GND7_P67") (pintype "passive"))
      (node (ref "U1") (pin "P81") (pinfunction "GND8_P81") (pintype "passive"))
      (node (ref "U1") (pin "P88") (pinfunction "GND9_P88") (pintype "passive"))
      (node (ref "U1") (pin "P9") (pinfunction "GND0_P9") (pintype "passive"))
      (node (ref "U1") (pin "P94") (pinfunction "GND10_P94") (pintype "passive"))
      (node (ref "X1") (pin "3") (pinfunction "2_3") (pintype "passive"))
      (node (ref "X2") (pin "13") (pinfunction "13_13") (pintype "passive"))
      (node (ref "X2") (pin "14") (pinfunction "14_14") (pintype "passive"))
      (node (ref "X2") (pin "17") (pinfunction "17_17") (pintype "passive"))
      (node (ref "X2") (pin "18") (pinfunction "18_18") (pintype "passive"))
      (node (ref "X2") (pin "21") (pinfunction "21_21") (pintype "passive"))
      (node (ref "X2") (pin "4") (pinfunction "4_4") (pintype "passive"))
      (node (ref "X2") (pin "5") (pinfunction "5_5") (pintype "passive"))
      (node (ref "X2") (pin "9") (pinfunction "9_9") (pintype "passive"))
      (node (ref "X3") (pin "3") (pinfunction "3_3") (pintype "passive"))
      (node (ref "X3") (pin "SH2") (pinfunction "PE2_SH2") (pintype "power_in"))
      (node (ref "X4") (pin "8") (pinfunction "F_8") (pintype "passive"))
      (node (ref "X4") (pin "G1") (pinfunction "G1_G1") (pintype "passive"))
      (node (ref "X5") (pin "8") (pinfunction "F_8") (pintype "passive"))
      (node (ref "X5") (pin "G1") (pinfunction "G1_G1") (pintype "passive"))
    )
    (net (code "68") (name "Net-(C1-Pad2)") (class "Default")
      (node (ref "C1") (pin "2") (pinfunction "2_2") (pintype "passive"))
      (node (ref "R23") (pin "2") (pinfunction "2_2") (pintype "passive"))
      (node (ref "R48") (pin "1") (pinfunction "1_1") (pintype "passive"))
    )
    (net (code "69") (name "Net-(C2-Pad1)") (class "Default")
      (node (ref "C2") (pin "1") (pinfunction "1_1") (pintype "passive"))
      (node (ref "R17") (pin "2") (pinfunction "2_2") (pintype "passive"))
      (node (ref "X1") (pin "1") (pinfunction "1_1") (pintype "passive"))
    )
    (net (code "70") (name "Net-(C3-Pad1)") (class "Default")
      (node (ref "C3") (pin "1") (pinfunction "1_1") (pintype "passive"))
      (node (ref "R48") (pin "2") (pinfunction "2_2") (pintype "passive"))
    )
    (net (code "71") (name "Net-(C4-Pad1)") (class "Default")
      (node (ref "C4") (pin "1") (pinfunction "1_1") (pintype "passive"))
      (node (ref "R49") (pin "2") (pinfunction "2_2") (pintype "passive"))
    )
    (net (code "72") (name "Net-(C5-Pad2)") (class "Default")
      (node (ref "C5") (pin "2") (pinfunction "2_2") (pintype "passive"))
      (node (ref "R34") (pin "2") (pinfunction "2_2") (pintype "passive"))
      (node (ref "R49") (pin "1") (pinfunction "1_1") (pintype "passive"))
    )
    (net (code "73") (name "Net-(IC1-CLK)") (class "Default")
      (node (ref "IC1") (pin "3") (pinfunction "CLK_3") (pintype "bidirectional"))
      (node (ref "U1") (pin "P72") (pinfunction "CCLK_P72") (pintype "bidirectional"))
    )
    (net (code "74") (name "Net-(IC1-TDO)") (class "Default")
      (node (ref "IC1") (pin "17") (pinfunction "TDO_17") (pintype "bidirectional"))
      (node (ref "R1") (pin "2") (pinfunction "2_2") (pintype "passive"))
    )
    (net (code "75") (name "Net-(IC1-{slash}CE)") (class "Default")
      (node (ref "IC1") (pin "10") (pinfunction "/CE_10") (pintype "bidirectional"))
      (node (ref "U1") (pin "P71") (pinfunction "DONE_P71") (pintype "bidirectional"))
    )
    (net (code "76") (name "Net-(IC1-{slash}CF)") (class "Default")
      (node (ref "IC1") (pin "7") (pinfunction "/CF_7") (pintype "bidirectional"))
      (node (ref "U1") (pin "P143") (pinfunction "PROG_B_P143") (pintype "bidirectional"))
    )
    (net (code "77") (name "Net-(Q5-B)") (class "Default")
      (node (ref "Q5") (pin "1") (pinfunction "B_1") (pintype "passive"))
      (node (ref "R8") (pin "2") (pinfunction "2_2") (pintype "passive"))
    )
    (net (code "78") (name "Net-(Q5-E)") (class "Default")
      (node (ref "Q5") (pin "2") (pinfunction "E_2") (pintype "passive"))
      (node (ref "R13") (pin "2") (pinfunction "2_2") (pintype "passive"))
      (node (ref "R14") (pin "2") (pinfunction "2_2") (pintype "passive"))
    )
    (net (code "79") (name "Net-(Q6-B)") (class "Default")
      (node (ref "Q6") (pin "1") (pinfunction "B_1") (pintype "passive"))
      (node (ref "R10") (pin "2") (pinfunction "2_2") (pintype "passive"))
      (node (ref "R9") (pin "2") (pinfunction "2_2") (pintype "passive"))
    )
    (net (code "80") (name "Net-(Q6-E)") (class "Default")
      (node (ref "Q6") (pin "2") (pinfunction "E_2") (pintype "passive"))
      (node (ref "R15") (pin "2") (pinfunction "2_2") (pintype "passive"))
      (node (ref "R16") (pin "2") (pinfunction "2_2") (pintype "passive"))
      (node (ref "R20") (pin "2") (pinfunction "2_2") (pintype "passive"))
    )
    (net (code "81") (name "Net-(Q7-B)") (class "Default")
      (node (ref "Q7") (pin "1") (pinfunction "B_1") (pintype "passive"))
      (node (ref "R29") (pin "2") (pinfunction "2_2") (pintype "passive"))
      (node (ref "R30") (pin "2") (pinfunction "2_2") (pintype "passive"))
    )
    (net (code "82") (name "Net-(Q7-E)") (class "Default")
      (node (ref "Q7") (pin "2") (pinfunction "E_2") (pintype "passive"))
      (node (ref "R31") (pin "2") (pinfunction "2_2") (pintype "passive"))
      (node (ref "R32") (pin "2") (pinfunction "2_2") (pintype "passive"))
      (node (ref "R33") (pin "2") (pinfunction "2_2") (pintype "passive"))
    )
    (net (code "83") (name "Net-(Q8-B)") (class "Default")
      (node (ref "Q8") (pin "1") (pinfunction "B_1") (pintype "passive"))
      (node (ref "R24") (pin "2") (pinfunction "2_2") (pintype "passive"))
      (node (ref "R25") (pin "2") (pinfunction "2_2") (pintype "passive"))
    )
    (net (code "84") (name "Net-(Q8-E)") (class "Default")
      (node (ref "Q8") (pin "2") (pinfunction "E_2") (pintype "passive"))
      (node (ref "R26") (pin "2") (pinfunction "2_2") (pintype "passive"))
      (node (ref "R27") (pin "2") (pinfunction "2_2") (pintype "passive"))
      (node (ref "R28") (pin "2") (pinfunction "2_2") (pintype "passive"))
    )
    (net (code "85") (name "Net-(R18-Pad2)") (class "Default")
      (node (ref "R18") (pin "2") (pinfunction "2_2") (pintype "passive"))
      (node (ref "R22") (pin "2") (pinfunction "2_2") (pintype "passive"))
    )
    (net (code "86") (name "Net-(T2-B)") (class "Default")
      (node (ref "C2") (pin "2") (pinfunction "2_2") (pintype "passive"))
      (node (ref "R18") (pin "1") (pinfunction "1_1") (pintype "passive"))
      (node (ref "R19") (pin "2") (pinfunction "2_2") (pintype "passive"))
      (node (ref "T2") (pin "1") (pinfunction "B_1") (pintype "passive"))
    )
    (net (code "87") (name "Net-(U$1-A0)") (class "Default")
      (node (ref "U$1") (pin "P20") (pinfunction "A0_P20") (pintype "bidirectional"))
      (node (ref "U1") (pin "P77") (pinfunction "IO_L20P_3_P77") (pintype "bidirectional"))
    )
    (net (code "88") (name "Net-(U$1-A1)") (class "Default")
      (node (ref "U$1") (pin "P19") (pinfunction "A1_P19") (pintype "bidirectional"))
      (node (ref "U1") (pin "P76") (pinfunction "IO_P76") (pintype "bidirectional"))
    )
    (net (code "89") (name "Net-(U$1-A2)") (class "Default")
      (node (ref "U$1") (pin "P18") (pinfunction "A2_P18") (pintype "bidirectional"))
      (node (ref "U1") (pin "P74") (pinfunction "IO_L01N_3VRP_3_P74") (pintype "bidirectional"))
    )
    (net (code "90") (name "Net-(U$1-A3)") (class "Default")
      (node (ref "U$1") (pin "P17") (pinfunction "A3_P17") (pintype "bidirectional"))
      (node (ref "U1") (pin "P73") (pinfunction "IO_L01P_3VRN_3_P73") (pintype "bidirectional"))
    )
    (net (code "91") (name "Net-(U$1-A4)") (class "Default")
      (node (ref "U$1") (pin "P16") (pinfunction "A4_P16") (pintype "bidirectional"))
      (node (ref "U1") (pin "P108") (pinfunction "IO_L01N_2VRP_2_P108") (pintype "bidirectional"))
    )
    (net (code "92") (name "Net-(U$1-A5)") (class "Default")
      (node (ref "U$1") (pin "P15") (pinfunction "A5_P15") (pintype "bidirectional"))
      (node (ref "U1") (pin "P107") (pinfunction "IO_L01P_2VRN_2_P107") (pintype "bidirectional"))
    )
    (net (code "93") (name "Net-(U$1-A6)") (class "Default")
      (node (ref "U$1") (pin "P14") (pinfunction "A6_P14") (pintype "bidirectional"))
      (node (ref "U1") (pin "P105") (pinfunction "IO_L20N_2_P105") (pintype "bidirectional"))
    )
    (net (code "94") (name "Net-(U$1-A7)") (class "Default")
      (node (ref "U$1") (pin "P13") (pinfunction "A7_P13") (pintype "bidirectional"))
      (node (ref "U1") (pin "P104") (pinfunction "IO_L20P_2_P104") (pintype "bidirectional"))
    )
    (net (code "95") (name "Net-(U$1-A8)") (class "Default")
      (node (ref "U$1") (pin "P3") (pinfunction "A8_P3") (pintype "bidirectional"))
      (node (ref "U1") (pin "P93") (pinfunction "IO_L40N_2_P93") (pintype "bidirectional"))
    )
    (net (code "96") (name "Net-(U$1-A9)") (class "Default")
      (node (ref "U$1") (pin "P2") (pinfunction "A9_P2") (pintype "bidirectional"))
      (node (ref "U1") (pin "P92") (pinfunction "IO_L40P_2VREF_2_P92") (pintype "bidirectional"))
    )
    (net (code "97") (name "Net-(U$1-A10)") (class "Default")
      (node (ref "U$1") (pin "P31") (pinfunction "A10_P31") (pintype "bidirectional"))
      (node (ref "U1") (pin "P87") (pinfunction "IO_L24N_3_P87") (pintype "bidirectional"))
    )
    (net (code "98") (name "Net-(U$1-A11)") (class "Default")
      (node (ref "U$1") (pin "P1") (pinfunction "A11_P1") (pintype "bidirectional"))
      (node (ref "U1") (pin "P90") (pinfunction "IO_L40N_3VREF_3_P90") (pintype "bidirectional"))
    )
    (net (code "99") (name "Net-(U$1-A12)") (class "Default")
      (node (ref "U$1") (pin "P12") (pinfunction "A12_P12") (pintype "bidirectional"))
      (node (ref "U1") (pin "P103") (pinfunction "IO_L21N_2_P103") (pintype "bidirectional"))
    )
    (net (code "100") (name "Net-(U$1-A13)") (class "Default")
      (node (ref "U$1") (pin "P4") (pinfunction "A13_P4") (pintype "bidirectional"))
      (node (ref "U1") (pin "P95") (pinfunction "IO_L24P_2_P95") (pintype "bidirectional"))
    )
    (net (code "101") (name "Net-(U$1-A14)") (class "Default")
      (node (ref "U$1") (pin "P11") (pinfunction "A14_P11") (pintype "bidirectional"))
      (node (ref "U1") (pin "P102") (pinfunction "IO_L21P_2_P102") (pintype "bidirectional"))
    )
    (net (code "102") (name "Net-(U$1-A15)") (class "Default")
      (node (ref "U$1") (pin "P7") (pinfunction "A15_P7") (pintype "bidirectional"))
      (node (ref "U1") (pin "P98") (pinfunction "IO_L23N_2VREF_2_P98") (pintype "bidirectional"))
    )
    (net (code "103") (name "Net-(U$1-A16)") (class "Default")
      (node (ref "U$1") (pin "P10") (pinfunction "A16_P10") (pintype "bidirectional"))
      (node (ref "U1") (pin "P100") (pinfunction "IO_L22N_2_P100") (pintype "bidirectional"))
    )
    (net (code "104") (name "Net-(U$1-A17)") (class "Default")
      (node (ref "U$1") (pin "P6") (pinfunction "A17_P6") (pintype "bidirectional"))
      (node (ref "U1") (pin "P97") (pinfunction "IO_L23P_2_P97") (pintype "bidirectional"))
    )
    (net (code "105") (name "Net-(U$1-A18)") (class "Default")
      (node (ref "U$1") (pin "P9") (pinfunction "A18_P9") (pintype "bidirectional"))
      (node (ref "U1") (pin "P99") (pinfunction "IO_L22P_2_P99") (pintype "bidirectional"))
    )
    (net (code "106") (name "Net-(U$1-DQ0)") (class "Default")
      (node (ref "U$1") (pin "P21") (pinfunction "DQ0_P21") (pintype "bidirectional"))
      (node (ref "U1") (pin "P78") (pinfunction "IO_L20N_3_P78") (pintype "bidirectional"))
    )
    (net (code "107") (name "Net-(U$1-DQ1)") (class "Default")
      (node (ref "U$1") (pin "P22") (pinfunction "DQ1_P22") (pintype "bidirectional"))
      (node (ref "U1") (pin "P79") (pinfunction "IO_L21P_3_P79") (pintype "bidirectional"))
    )
    (net (code "108") (name "Net-(U$1-DQ2)") (class "Default")
      (node (ref "U$1") (pin "P23") (pinfunction "DQ2_P23") (pintype "bidirectional"))
      (node (ref "U1") (pin "P80") (pinfunction "IO_L21N_3_P80") (pintype "bidirectional"))
    )
    (net (code "109") (name "Net-(U$1-DQ3)") (class "Default")
      (node (ref "U$1") (pin "P25") (pinfunction "DQ3_P25") (pintype "bidirectional"))
      (node (ref "U1") (pin "P82") (pinfunction "IO_L22P_3_P82") (pintype "bidirectional"))
    )
    (net (code "110") (name "Net-(U$1-DQ4)") (class "Default")
      (node (ref "U$1") (pin "P26") (pinfunction "DQ4_P26") (pintype "bidirectional"))
      (node (ref "U1") (pin "P83") (pinfunction "IO_L22N_3_P83") (pintype "bidirectional"))
    )
    (net (code "111") (name "Net-(U$1-DQ5)") (class "Default")
      (node (ref "U$1") (pin "P27") (pinfunction "DQ5_P27") (pintype "bidirectional"))
      (node (ref "U1") (pin "P84") (pinfunction "IO_L23P_3VREF_3_P84") (pintype "bidirectional"))
    )
    (net (code "112") (name "Net-(U$1-DQ6)") (class "Default")
      (node (ref "U$1") (pin "P28") (pinfunction "DQ6_P28") (pintype "bidirectional"))
      (node (ref "U1") (pin "P85") (pinfunction "IO_L23N_3_P85") (pintype "bidirectional"))
    )
    (net (code "113") (name "Net-(U$1-DQ7)") (class "Default")
      (node (ref "U$1") (pin "P29") (pinfunction "DQ7_P29") (pintype "bidirectional"))
      (node (ref "U1") (pin "P86") (pinfunction "IO_L24P_3_P86") (pintype "bidirectional"))
    )
    (net (code "114") (name "Net-(U$1-OE)") (class "Default")
      (node (ref "U$1") (pin "P32") (pinfunction "OE_P32") (pintype "bidirectional"))
      (node (ref "U1") (pin "P89") (pinfunction "IO_L40P_3_P89") (pintype "bidirectional"))
    )
    (net (code "115") (name "Net-(U$1-WE)") (class "Default")
      (node (ref "U$1") (pin "P5") (pinfunction "WE_P5") (pintype "bidirectional"))
      (node (ref "U1") (pin "P96") (pinfunction "IO_L24N_2_P96") (pintype "bidirectional"))
    )
    (net (code "116") (name "Net-(U1N-TCK)") (class "Default")
      (node (ref "R2") (pin "1") (pinfunction "1_1") (pintype "passive"))
      (node (ref "U1") (pin "P110") (pinfunction "TCK_P110") (pintype "bidirectional"))
    )
    (net (code "117") (name "Net-(U1N-TDI)") (class "Default")
      (node (ref "R1") (pin "1") (pinfunction "1_1") (pintype "passive"))
      (node (ref "U1") (pin "P144") (pinfunction "TDI_P144") (pintype "bidirectional"))
    )
    (net (code "118") (name "Net-(U1N-TMS)") (class "Default")
      (node (ref "R3") (pin "1") (pinfunction "1_1") (pintype "passive"))
      (node (ref "U1") (pin "P111") (pinfunction "TMS_P111") (pintype "bidirectional"))
    )
    (net (code "119") (name "Net-(X4A-F)") (class "Default")
      (node (ref "R40") (pin "2") (pinfunction "2_2") (pintype "passive"))
      (node (ref "X4") (pin "1") (pinfunction "F_1") (pintype "passive"))
    )
    (net (code "120") (name "Net-(X4B-F)") (class "Default")
      (node (ref "R41") (pin "2") (pinfunction "2_2") (pintype "passive"))
      (node (ref "X4") (pin "2") (pinfunction "F_2") (pintype "passive"))
    )
    (net (code "121") (name "Net-(X4C-F)") (class "Default")
      (node (ref "R42") (pin "2") (pinfunction "2_2") (pintype "passive"))
      (node (ref "X4") (pin "3") (pinfunction "F_3") (pintype "passive"))
    )
    (net (code "122") (name "Net-(X4D-F)") (class "Default")
      (node (ref "R43") (pin "2") (pinfunction "2_2") (pintype "passive"))
      (node (ref "X4") (pin "4") (pinfunction "F_4") (pintype "passive"))
    )
    (net (code "123") (name "Net-(X4F-F)") (class "Default")
      (node (ref "R44") (pin "2") (pinfunction "2_2") (pintype "passive"))
      (node (ref "X4") (pin "6") (pinfunction "F_6") (pintype "passive"))
    )
    (net (code "124") (name "Net-(X4G-F)") (class "Default")
      (node (ref "R45") (pin "2") (pinfunction "2_2") (pintype "passive"))
      (node (ref "X4") (pin "7") (pinfunction "F_7") (pintype "passive"))
    )
    (net (code "125") (name "Net-(X5A-F)") (class "Default")
      (node (ref "R46") (pin "1") (pinfunction "1_1") (pintype "passive"))
      (node (ref "X5") (pin "1") (pinfunction "F_1") (pintype "passive"))
    )
    (net (code "126") (name "Net-(X5B-F)") (class "Default")
      (node (ref "R39") (pin "1") (pinfunction "1_1") (pintype "passive"))
      (node (ref "X5") (pin "2") (pinfunction "F_2") (pintype "passive"))
    )
    (net (code "127") (name "Net-(X5C-F)") (class "Default")
      (node (ref "R38") (pin "1") (pinfunction "1_1") (pintype "passive"))
      (node (ref "X5") (pin "3") (pinfunction "F_3") (pintype "passive"))
    )
    (net (code "128") (name "Net-(X5D-F)") (class "Default")
      (node (ref "R37") (pin "1") (pinfunction "1_1") (pintype "passive"))
      (node (ref "X5") (pin "4") (pinfunction "F_4") (pintype "passive"))
    )
    (net (code "129") (name "Net-(X5F-F)") (class "Default")
      (node (ref "R36") (pin "1") (pinfunction "1_1") (pintype "passive"))
      (node (ref "X5") (pin "6") (pinfunction "F_6") (pintype "passive"))
    )
    (net (code "130") (name "Net-(X5G-F)") (class "Default")
      (node (ref "R35") (pin "1") (pinfunction "1_1") (pintype "passive"))
      (node (ref "X5") (pin "7") (pinfunction "F_7") (pintype "passive"))
    )
    (net (code "131") (name "unconnected-(IC1-NC.1-Pad2)") (class "Default")
      (node (ref "IC1") (pin "2") (pinfunction "NC.1_2") (pintype "bidirectional"))
    )
    (net (code "132") (name "unconnected-(IC1-NC.2-Pad9)") (class "Default")
      (node (ref "IC1") (pin "9") (pinfunction "NC.2_9") (pintype "bidirectional"))
    )
    (net (code "133") (name "unconnected-(IC1-NC.3-Pad12)") (class "Default")
      (node (ref "IC1") (pin "12") (pinfunction "NC.3_12") (pintype "bidirectional"))
    )
    (net (code "134") (name "unconnected-(IC1-NC.4-Pad14)") (class "Default")
      (node (ref "IC1") (pin "14") (pinfunction "NC.4_14") (pintype "bidirectional"))
    )
    (net (code "135") (name "unconnected-(IC1-NC.5-Pad15)") (class "Default")
      (node (ref "IC1") (pin "15") (pinfunction "NC.5_15") (pintype "bidirectional"))
    )
    (net (code "136") (name "unconnected-(IC1-NC.6-Pad16)") (class "Default")
      (node (ref "IC1") (pin "16") (pinfunction "NC.6_16") (pintype "bidirectional"))
    )
    (net (code "137") (name "unconnected-(IC1-{slash}CEO-Pad13)") (class "Default")
      (node (ref "IC1") (pin "13") (pinfunction "/CEO_13") (pintype "bidirectional"))
    )
    (net (code "138") (name "unconnected-(IC3-AVCC-Pad32)") (class "Default")
      (node (ref "IC3") (pin "32") (pinfunction "AVCC_32") (pintype "bidirectional"))
    )
    (net (code "139") (name "unconnected-(IC3-D+-Pad29)") (class "Default")
      (node (ref "IC3") (pin "29") (pinfunction "D+_29") (pintype "bidirectional"))
    )
    (net (code "140") (name "unconnected-(IC3-D--Pad30)") (class "Default")
      (node (ref "IC3") (pin "30") (pinfunction "D-_30") (pintype "bidirectional"))
    )
    (net (code "141") (name "unconnected-(IC3-GND-Pad3)") (class "Default")
      (node (ref "IC3") (pin "3") (pinfunction "GND_3") (pintype "bidirectional"))
    )
    (net (code "142") (name "unconnected-(IC3-PB4(T1{slash}PCINT4)-Pad18)") (class "Default")
      (node (ref "IC3") (pin "18") (pinfunction "PB4(T1/PCINT4)_18") (pintype "bidirectional"))
    )
    (net (code "143") (name "unconnected-(IC3-PB5(PCINT5)-Pad19)") (class "Default")
      (node (ref "IC3") (pin "19") (pinfunction "PB5(PCINT5)_19") (pintype "bidirectional"))
    )
    (net (code "144") (name "unconnected-(IC3-PB6(PCINT6)-Pad20)") (class "Default")
      (node (ref "IC3") (pin "20") (pinfunction "PB6(PCINT6)_20") (pintype "bidirectional"))
    )
    (net (code "145") (name "unconnected-(IC3-PB7(OC0A{slash}OC1C{slash}PCINT7)-Pad21)") (class "Default")
      (node (ref "IC3") (pin "21") (pinfunction "PB7(OC0A/OC1C/PCINT7)_21") (pintype "bidirectional"))
    )
    (net (code "146") (name "unconnected-(IC3-PC2(AIN2{slash}PCIN11)-Pad5)") (class "Default")
      (node (ref "IC3") (pin "5") (pinfunction "PC2(AIN2/PCIN11)_5") (pintype "bidirectional"))
    )
    (net (code "147") (name "unconnected-(IC3-PC4(PCINT10)-Pad26)") (class "Default")
      (node (ref "IC3") (pin "26") (pinfunction "PC4(PCINT10)_26") (pintype "bidirectional"))
    )
    (net (code "148") (name "unconnected-(IC3-PC5(OC1B{slash}PCINT9)-Pad25)") (class "Default")
      (node (ref "IC3") (pin "25") (pinfunction "PC5(OC1B/PCINT9)_25") (pintype "bidirectional"))
    )
    (net (code "149") (name "unconnected-(IC3-PC6(OC1A{slash}PCINT8)-Pad23)") (class "Default")
      (node (ref "IC3") (pin "23") (pinfunction "PC6(OC1A/PCINT8)_23") (pintype "bidirectional"))
    )
    (net (code "150") (name "unconnected-(IC3-PC7(ICP1{slash}INT4{slash}CLKO)-Pad22)") (class "Default")
      (node (ref "IC3") (pin "22") (pinfunction "PC7(ICP1/INT4/CLKO)_22") (pintype "bidirectional"))
    )
    (net (code "151") (name "unconnected-(IC3-PD0(INT0{slash}OC0B)-Pad6)") (class "Default")
      (node (ref "IC3") (pin "6") (pinfunction "PD0(INT0/OC0B)_6") (pintype "bidirectional"))
    )
    (net (code "152") (name "unconnected-(IC3-PD1(INT1{slash}AIN0)-Pad7)") (class "Default")
      (node (ref "IC3") (pin "7") (pinfunction "PD1(INT1/AIN0)_7") (pintype "bidirectional"))
    )
    (net (code "153") (name "unconnected-(IC3-PD4(INT5{slash}AIN3)-Pad10)") (class "Default")
      (node (ref "IC3") (pin "10") (pinfunction "PD4(INT5/AIN3)_10") (pintype "bidirectional"))
    )
    (net (code "154") (name "unconnected-(IC3-PD5(XCK{slash}AIN4{slash}PCINT12)-Pad11)") (class "Default")
      (node (ref "IC3") (pin "11") (pinfunction "PD5(XCK/AIN4/PCINT12)_11") (pintype "bidirectional"))
    )
    (net (code "155") (name "unconnected-(IC3-PD6(INT6{slash}AIN5{slash}RTS)-Pad12)") (class "Default")
      (node (ref "IC3") (pin "12") (pinfunction "PD6(INT6/AIN5/RTS)_12") (pintype "bidirectional"))
    )
    (net (code "156") (name "unconnected-(IC3-UCAP-Pad27)") (class "Default")
      (node (ref "IC3") (pin "27") (pinfunction "UCAP_27") (pintype "bidirectional"))
    )
    (net (code "157") (name "unconnected-(IC3-UGND-Pad28)") (class "Default")
      (node (ref "IC3") (pin "28") (pinfunction "UGND_28") (pintype "bidirectional"))
    )
    (net (code "158") (name "unconnected-(IC3-UVCC-Pad31)") (class "Default")
      (node (ref "IC3") (pin "31") (pinfunction "UVCC_31") (pintype "bidirectional"))
    )
    (net (code "159") (name "unconnected-(IC3-VCC-Pad4)") (class "Default")
      (node (ref "IC3") (pin "4") (pinfunction "VCC_4") (pintype "bidirectional"))
    )
    (net (code "160") (name "unconnected-(IC3-XTAL1-Pad1)") (class "Default")
      (node (ref "IC3") (pin "1") (pinfunction "XTAL1_1") (pintype "bidirectional"))
    )
    (net (code "161") (name "unconnected-(IC3-XTAL2{slash}PC0-Pad2)") (class "Default")
      (node (ref "IC3") (pin "2") (pinfunction "XTAL2/PC0_2") (pintype "bidirectional"))
    )
    (net (code "162") (name "unconnected-(IC3-{slash}RESET(PC1)-Pad24)") (class "Default")
      (node (ref "IC3") (pin "24") (pinfunction "/RESET(PC1)_24") (pintype "bidirectional"))
    )
    (net (code "163") (name "unconnected-(REG1.2-VOUT2-Pad2)") (class "Default")
      (node (ref "REG1.2") (pin "2") (pinfunction "VOUT2_2") (pintype "bidirectional"))
    )
    (net (code "164") (name "unconnected-(U$2-TRI-PadENA)") (class "Default")
      (node (ref "U$2") (pin "ENA") (pinfunction "TRI_ENA") (pintype "input"))
    )
    (net (code "165") (name "unconnected-(U1A-IO_L27P_0-PadP135)") (class "Default")
      (node (ref "U1") (pin "P135") (pinfunction "IO_L27P_0_P135") (pintype "bidirectional"))
    )
    (net (code "166") (name "unconnected-(U1A-IO_L30N_0-PadP132)") (class "Default")
      (node (ref "U1") (pin "P132") (pinfunction "IO_L30N_0_P132") (pintype "bidirectional"))
    )
    (net (code "167") (name "unconnected-(U1A-IO_L30P_0-PadP131)") (class "Default")
      (node (ref "U1") (pin "P131") (pinfunction "IO_L30P_0_P131") (pintype "bidirectional"))
    )
    (net (code "168") (name "unconnected-(U1A-IO_L31N_0-PadP130)") (class "Default")
      (node (ref "U1") (pin "P130") (pinfunction "IO_L31N_0_P130") (pintype "bidirectional"))
    )
    (net (code "169") (name "unconnected-(U1A-IO_L31P_0VREF_0-PadP129)") (class "Default")
      (node (ref "U1") (pin "P129") (pinfunction "IO_L31P_0VREF_0_P129") (pintype "bidirectional"))
    )
    (net (code "170") (name "unconnected-(U1A-IO_L32N_0GCLK7-PadP128)") (class "Default")
      (node (ref "U1") (pin "P128") (pinfunction "IO_L32N_0GCLK7_P128") (pintype "bidirectional"))
    )
    (net (code "171") (name "unconnected-(U1A-IO_L32P_0GCLK6-PadP127)") (class "Default")
      (node (ref "U1") (pin "P127") (pinfunction "IO_L32P_0GCLK6_P127") (pintype "bidirectional"))
    )
    (net (code "172") (name "unconnected-(U1C-IO-PadP116)") (class "Default")
      (node (ref "U1") (pin "P116") (pinfunction "IO_P116") (pintype "bidirectional"))
    )
    (net (code "173") (name "unconnected-(U1C-IO_L01N_1VRP_1-PadP113)") (class "Default")
      (node (ref "U1") (pin "P113") (pinfunction "IO_L01N_1VRP_1_P113") (pintype "bidirectional"))
    )
    (net (code "174") (name "unconnected-(U1C-IO_L01P_1VRN_1-PadP112)") (class "Default")
      (node (ref "U1") (pin "P112") (pinfunction "IO_L01P_1VRN_1_P112") (pintype "bidirectional"))
    )
    (net (code "175") (name "unconnected-(U1C-IO_L28N_1-PadP119)") (class "Default")
      (node (ref "U1") (pin "P119") (pinfunction "IO_L28N_1_P119") (pintype "bidirectional"))
    )
    (net (code "176") (name "unconnected-(U1C-IO_L28P_1-PadP118)") (class "Default")
      (node (ref "U1") (pin "P118") (pinfunction "IO_L28P_1_P118") (pintype "bidirectional"))
    )
    (net (code "177") (name "unconnected-(U1C-IO_L31N_1VREF_1-PadP123)") (class "Default")
      (node (ref "U1") (pin "P123") (pinfunction "IO_L31N_1VREF_1_P123") (pintype "bidirectional"))
    )
    (net (code "178") (name "unconnected-(U1C-IO_L31P_1-PadP122)") (class "Default")
      (node (ref "U1") (pin "P122") (pinfunction "IO_L31P_1_P122") (pintype "bidirectional"))
    )
    (net (code "179") (name "unconnected-(U1C-IO_L32N_1GCLK5-PadP125)") (class "Default")
      (node (ref "U1") (pin "P125") (pinfunction "IO_L32N_1GCLK5_P125") (pintype "bidirectional"))
    )
    (net (code "180") (name "unconnected-(U1C-IO_L32P_1GCLK4-PadP124)") (class "Default")
      (node (ref "U1") (pin "P124") (pinfunction "IO_L32P_1GCLK4_P124") (pintype "bidirectional"))
    )
    (net (code "181") (name "unconnected-(U1J-IO_L01N_6VRP_6-PadP36)") (class "Default")
      (node (ref "U1") (pin "P36") (pinfunction "IO_L01N_6VRP_6_P36") (pintype "bidirectional"))
    )
    (net (code "182") (name "unconnected-(U1J-IO_L01P_6VRN_6-PadP35)") (class "Default")
      (node (ref "U1") (pin "P35") (pinfunction "IO_L01P_6VRN_6_P35") (pintype "bidirectional"))
    )
    (net (code "183") (name "unconnected-(U1J-IO_L20N_6-PadP33)") (class "Default")
      (node (ref "U1") (pin "P33") (pinfunction "IO_L20N_6_P33") (pintype "bidirectional"))
    )
    (net (code "184") (name "unconnected-(U1J-IO_L20P_6-PadP32)") (class "Default")
      (node (ref "U1") (pin "P32") (pinfunction "IO_L20P_6_P32") (pintype "bidirectional"))
    )
    (net (code "185") (name "unconnected-(U1J-IO_L21N_6-PadP31)") (class "Default")
      (node (ref "U1") (pin "P31") (pinfunction "IO_L21N_6_P31") (pintype "bidirectional"))
    )
    (net (code "186") (name "unconnected-(U1J-IO_L21P_6-PadP30)") (class "Default")
      (node (ref "U1") (pin "P30") (pinfunction "IO_L21P_6_P30") (pintype "bidirectional"))
    )
    (net (code "187") (name "unconnected-(U1J-IO_L22N_6-PadP28)") (class "Default")
      (node (ref "U1") (pin "P28") (pinfunction "IO_L22N_6_P28") (pintype "bidirectional"))
    )
    (net (code "188") (name "unconnected-(U1J-IO_L22P_6-PadP27)") (class "Default")
      (node (ref "U1") (pin "P27") (pinfunction "IO_L22P_6_P27") (pintype "bidirectional"))
    )
    (net (code "189") (name "unconnected-(U1J-IO_L23N_6-PadP26)") (class "Default")
      (node (ref "U1") (pin "P26") (pinfunction "IO_L23N_6_P26") (pintype "bidirectional"))
    )
    (net (code "190") (name "unconnected-(U1J-IO_L23P_6-PadP25)") (class "Default")
      (node (ref "U1") (pin "P25") (pinfunction "IO_L23P_6_P25") (pintype "bidirectional"))
    )
    (net (code "191") (name "unconnected-(U1J-IO_L24N_6VREF_6-PadP24)") (class "Default")
      (node (ref "U1") (pin "P24") (pinfunction "IO_L24N_6VREF_6_P24") (pintype "bidirectional"))
    )
    (net (code "192") (name "unconnected-(U1J-IO_L24P_6-PadP23)") (class "Default")
      (node (ref "U1") (pin "P23") (pinfunction "IO_L24P_6_P23") (pintype "bidirectional"))
    )
    (net (code "193") (name "unconnected-(U1J-IO_L40N_6-PadP21)") (class "Default")
      (node (ref "U1") (pin "P21") (pinfunction "IO_L40N_6_P21") (pintype "bidirectional"))
    )
    (net (code "194") (name "unconnected-(U1J-IO_L40P_6VREF_6-PadP20)") (class "Default")
      (node (ref "U1") (pin "P20") (pinfunction "IO_L40P_6VREF_6_P20") (pintype "bidirectional"))
    )
    (net (code "195") (name "unconnected-(U1L-IOVREF_7-PadP4)") (class "Default")
      (node (ref "U1") (pin "P4") (pinfunction "IOVREF_7_P4") (pintype "bidirectional"))
    )
    (net (code "196") (name "unconnected-(U1L-IO_L01N_7VRP_7-PadP2)") (class "Default")
      (node (ref "U1") (pin "P2") (pinfunction "IO_L01N_7VRP_7_P2") (pintype "bidirectional"))
    )
    (net (code "197") (name "unconnected-(U1L-IO_L01P_7VRN_7-PadP1)") (class "Default")
      (node (ref "U1") (pin "P1") (pinfunction "IO_L01P_7VRN_7_P1") (pintype "bidirectional"))
    )
    (net (code "198") (name "unconnected-(U1L-IO_L20N_7-PadP6)") (class "Default")
      (node (ref "U1") (pin "P6") (pinfunction "IO_L20N_7_P6") (pintype "bidirectional"))
    )
    (net (code "199") (name "unconnected-(U1L-IO_L20P_7-PadP5)") (class "Default")
      (node (ref "U1") (pin "P5") (pinfunction "IO_L20P_7_P5") (pintype "bidirectional"))
    )
    (net (code "200") (name "unconnected-(U1L-IO_L21N_7-PadP8)") (class "Default")
      (node (ref "U1") (pin "P8") (pinfunction "IO_L21N_7_P8") (pintype "bidirectional"))
    )
    (net (code "201") (name "unconnected-(U1L-IO_L21P_7-PadP7)") (class "Default")
      (node (ref "U1") (pin "P7") (pinfunction "IO_L21P_7_P7") (pintype "bidirectional"))
    )
    (net (code "202") (name "unconnected-(U1L-IO_L22N_7-PadP11)") (class "Default")
      (node (ref "U1") (pin "P11") (pinfunction "IO_L22N_7_P11") (pintype "bidirectional"))
    )
    (net (code "203") (name "unconnected-(U1L-IO_L22P_7-PadP10)") (class "Default")
      (node (ref "U1") (pin "P10") (pinfunction "IO_L22P_7_P10") (pintype "bidirectional"))
    )
    (net (code "204") (name "unconnected-(U1L-IO_L23N_7-PadP13)") (class "Default")
      (node (ref "U1") (pin "P13") (pinfunction "IO_L23N_7_P13") (pintype "bidirectional"))
    )
    (net (code "205") (name "unconnected-(U1L-IO_L23P_7-PadP12)") (class "Default")
      (node (ref "U1") (pin "P12") (pinfunction "IO_L23P_7_P12") (pintype "bidirectional"))
    )
    (net (code "206") (name "unconnected-(U1L-IO_L24N_7-PadP15)") (class "Default")
      (node (ref "U1") (pin "P15") (pinfunction "IO_L24N_7_P15") (pintype "bidirectional"))
    )
    (net (code "207") (name "unconnected-(U1L-IO_L24P_7-PadP14)") (class "Default")
      (node (ref "U1") (pin "P14") (pinfunction "IO_L24P_7_P14") (pintype "bidirectional"))
    )
    (net (code "208") (name "unconnected-(U1L-IO_L40N_7VREF_7-PadP18)") (class "Default")
      (node (ref "U1") (pin "P18") (pinfunction "IO_L40N_7VREF_7_P18") (pintype "bidirectional"))
    )
    (net (code "209") (name "unconnected-(U1L-IO_L40P_7-PadP17)") (class "Default")
      (node (ref "U1") (pin "P17") (pinfunction "IO_L40P_7_P17") (pintype "bidirectional"))
    )
    (net (code "210") (name "unconnected-(U1N-HSWAP_EN-PadP142)") (class "Default")
      (node (ref "U1") (pin "P142") (pinfunction "HSWAP_EN_P142") (pintype "bidirectional"))
    )
    (net (code "211") (name "unconnected-(X1-3-Pad2)") (class "Default")
      (node (ref "X1") (pin "2") (pinfunction "3_2") (pintype "passive"))
    )
    (net (code "212") (name "unconnected-(X2-Pad10)") (class "Default")
      (node (ref "X2") (pin "10") (pinfunction "10_10") (pintype "passive"))
    )
    (net (code "213") (name "unconnected-(X2-Pad12)") (class "Default")
      (node (ref "X2") (pin "12") (pinfunction "12_12") (pintype "passive"))
    )
    (net (code "214") (name "unconnected-(X3-Pad2)") (class "Default")
      (node (ref "X3") (pin "2") (pinfunction "2_2") (pintype "passive"))
    )
    (net (code "215") (name "unconnected-(X3-Pad8)") (class "Default")
      (node (ref "X3") (pin "8") (pinfunction "8_8") (pintype "passive"))
    )
    (net (code "216") (name "unconnected-(X4-PadG2)") (class "Default")
      (node (ref "X4") (pin "G2") (pinfunction "G2_G2") (pintype "passive"))
    )
    (net (code "217") (name "unconnected-(X5-PadG2)") (class "Default")
      (node (ref "X5") (pin "G2") (pinfunction "G2_G2") (pintype "passive"))
    )
  )
)
